# Sensor_Board.net
KiCad netlist of a schematic drawn in EAGLE
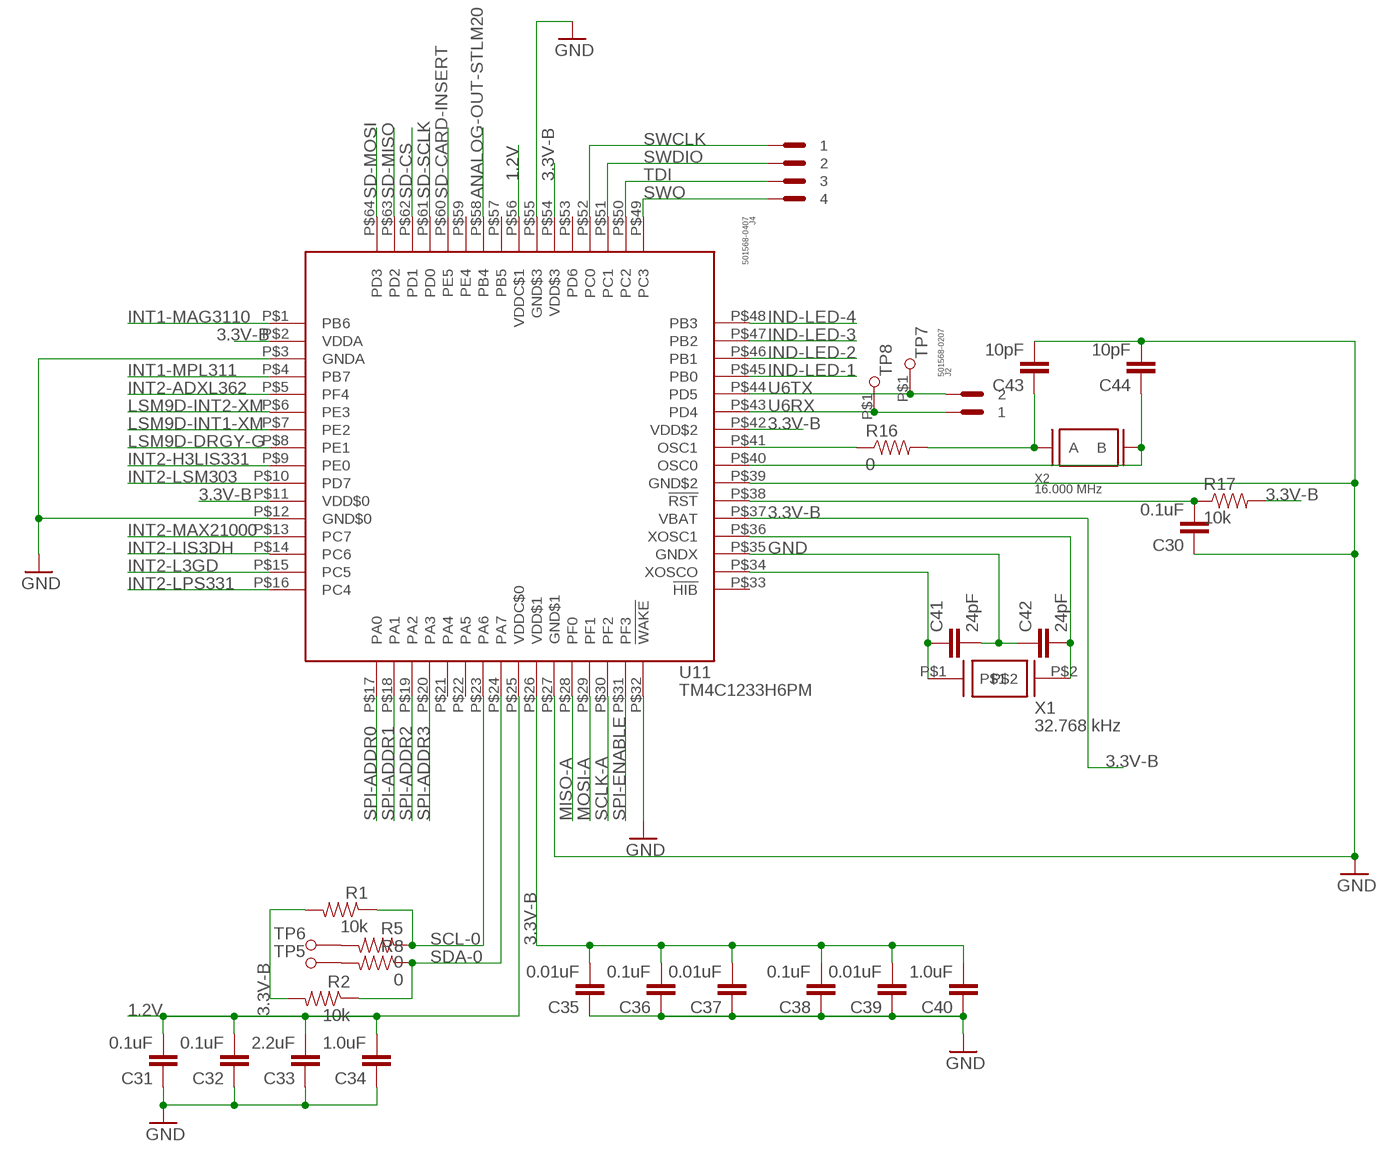
[diagram p0: schematic, sheet 1]
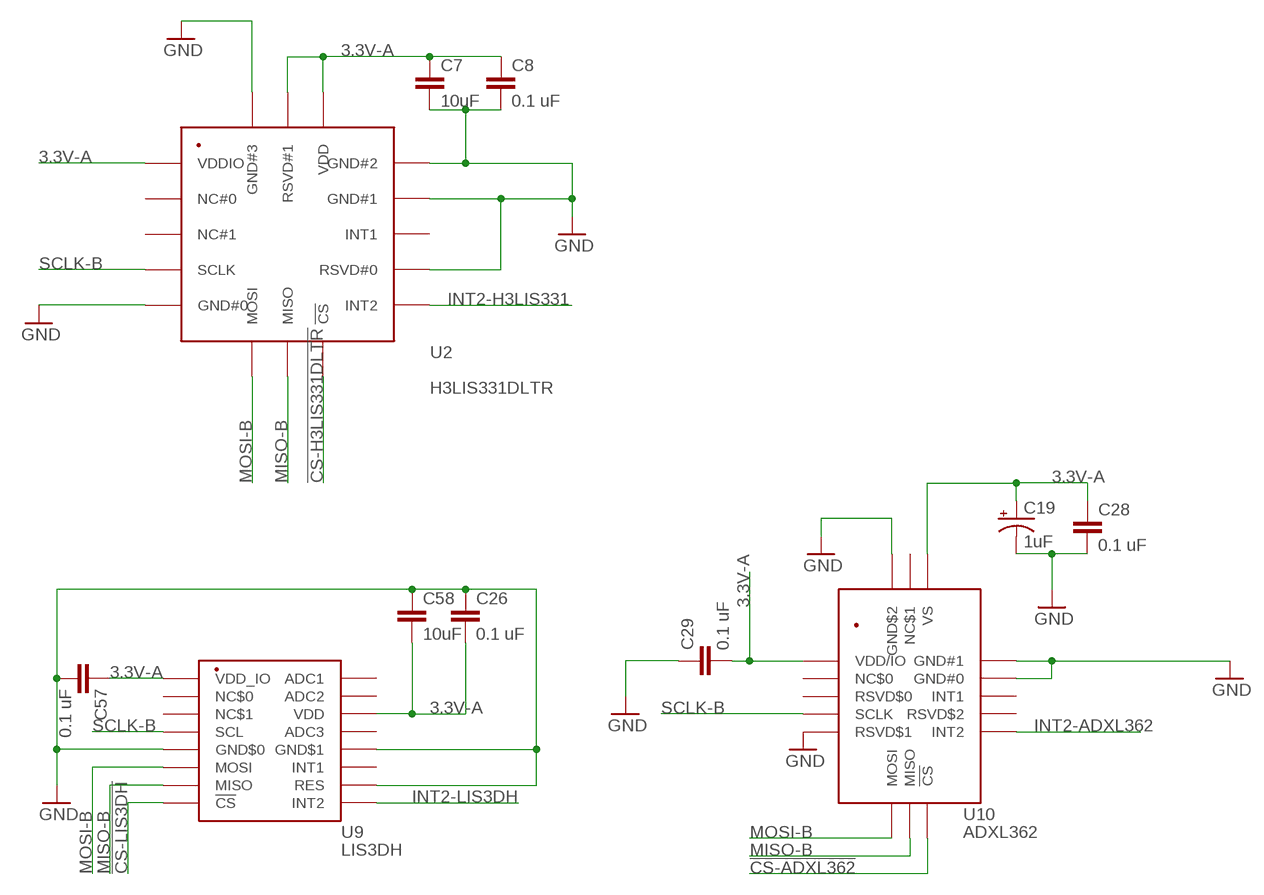
[diagram p1: schematic, sheet 2]
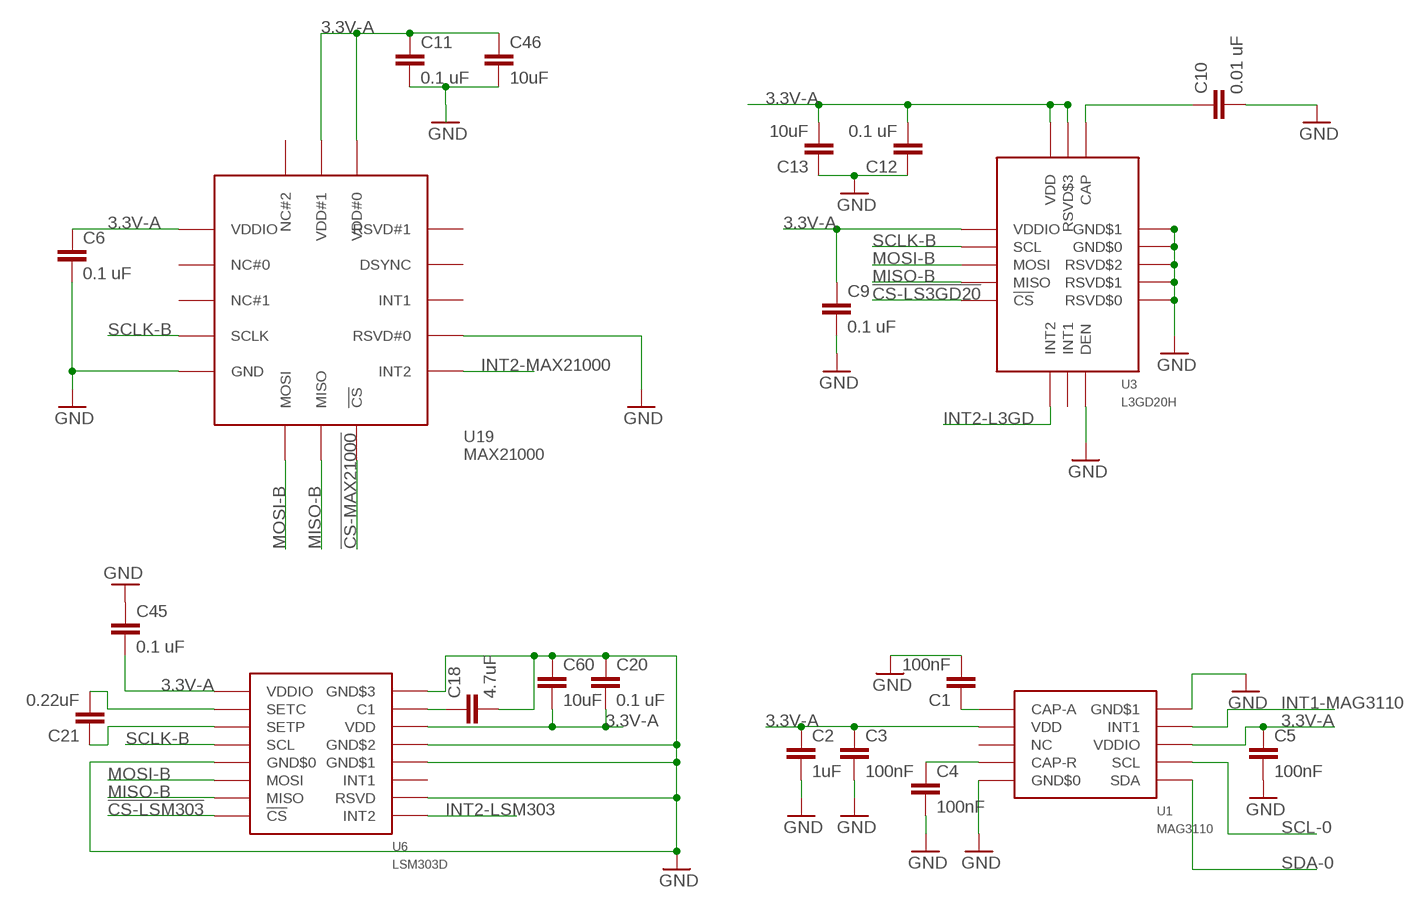
[diagram p2: schematic, sheet 3]
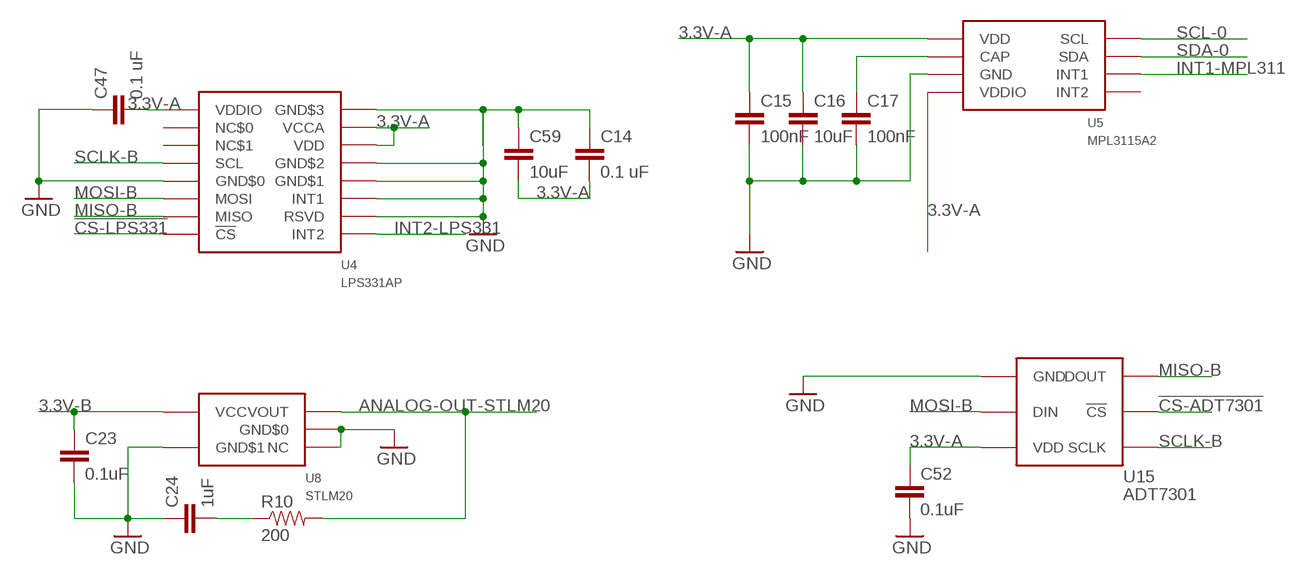
[diagram p3: schematic, sheet 4]
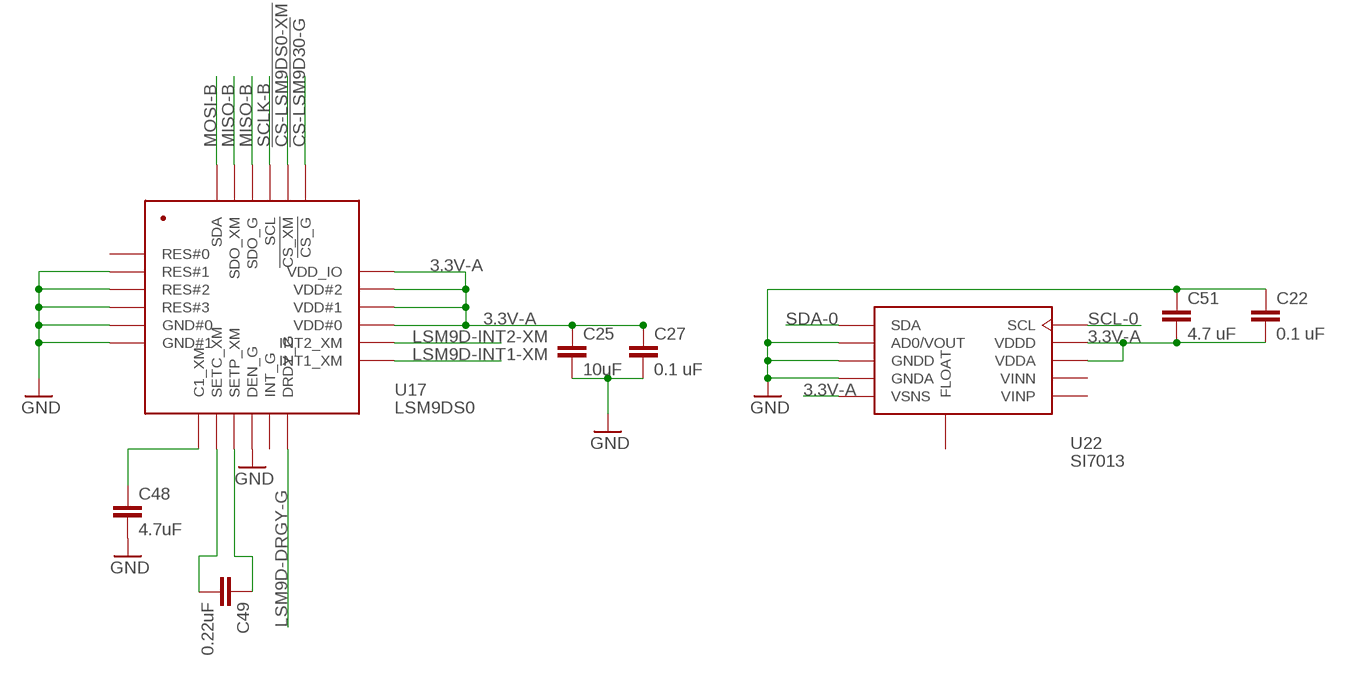
[diagram p4: schematic, sheet 5]
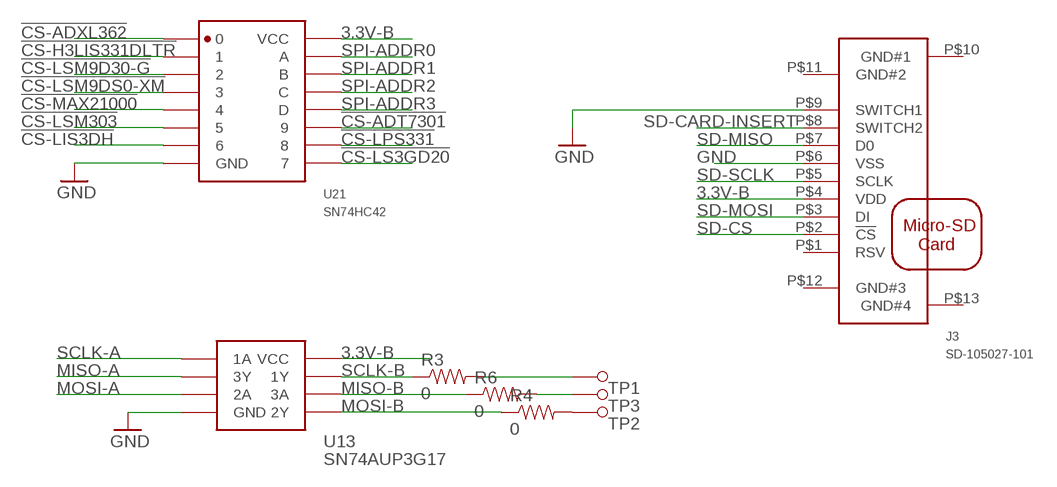
[diagram p5: schematic, sheet 6]
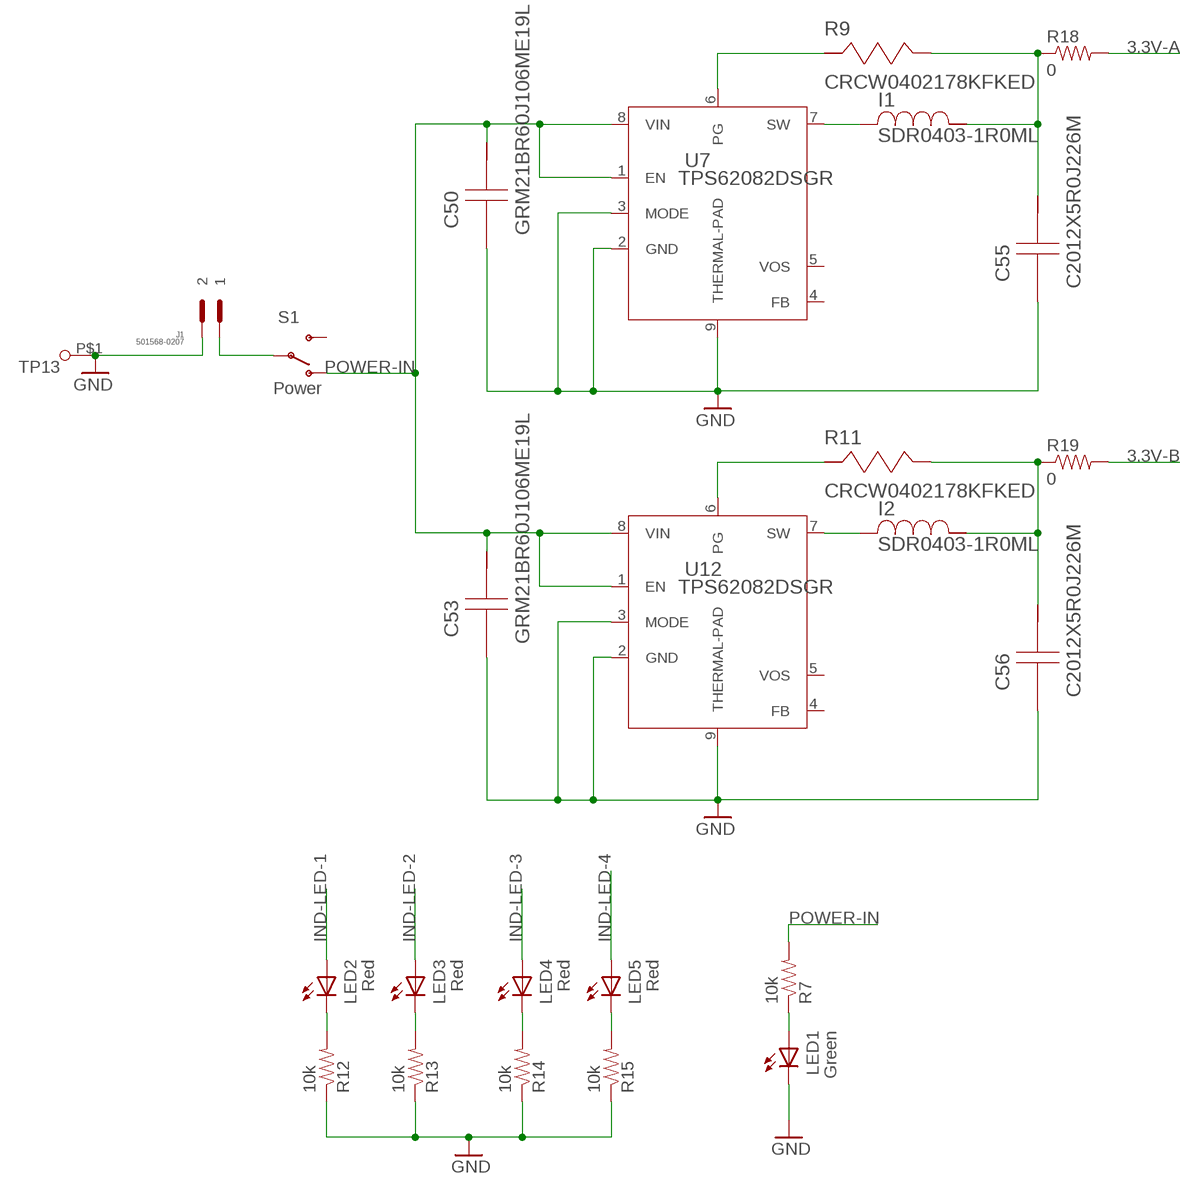
[diagram p6: schematic, sheet 7]

(export (version "E")
  (design (tool "Eeschema 10.0.6"))
  (components
    (comp (ref "J3")
      (value "SD-105027-101")
      (footprint "eagle-import:SD-105027-1001")
      (libsource (lib "eagle-import") (part "SD-105027-101"))
    )
    (comp (ref "R3")
      (value "0")
      (footprint "eagle-import:R0402")
      (libsource (lib "eagle-import") (part "RESISTOR"))
    )
    (comp (ref "R4")
      (value "0")
      (footprint "eagle-import:R0402")
      (libsource (lib "eagle-import") (part "RESISTOR"))
    )
    (comp (ref "R6")
      (value "0")
      (footprint "eagle-import:R0402")
      (libsource (lib "eagle-import") (part "RESISTOR"))
    )
    (comp (ref "TP1")
      (value "TESTPAD(ROUND)")
      (footprint "eagle-import:TESTPAD(ROUND)")
      (libsource (lib "eagle-import") (part "TESTPAD(ROUND)"))
    )
    (comp (ref "TP2")
      (value "TESTPAD(ROUND)")
      (footprint "eagle-import:TESTPAD(ROUND)")
      (libsource (lib "eagle-import") (part "TESTPAD(ROUND)"))
    )
    (comp (ref "TP3")
      (value "TESTPAD(ROUND)")
      (footprint "eagle-import:TESTPAD(ROUND)")
      (libsource (lib "eagle-import") (part "TESTPAD(ROUND)"))
    )
    (comp (ref "U13")
      (value "SN74AUP3G17")
      (footprint "eagle-import:8-VFSOP")
      (libsource (lib "eagle-import") (part "SN74AUP3G17"))
    )
    (comp (ref "U21")
      (value "SN74HC42")
      (footprint "eagle-import:SOIC-16")
      (libsource (lib "eagle-import") (part "SN74HC42"))
    )
    (comp (ref "C1")
      (value "100nF")
      (footprint "eagle-import:C0402")
      (libsource (lib "eagle-import") (part "CAPACITOR0402"))
    )
    (comp (ref "C2")
      (value "1uF")
      (footprint "eagle-import:C0402")
      (libsource (lib "eagle-import") (part "CAPACITOR0402"))
    )
    (comp (ref "C3")
      (value "100nF")
      (footprint "eagle-import:C0402")
      (libsource (lib "eagle-import") (part "CAPACITOR0402"))
    )
    (comp (ref "C4")
      (value "100nF")
      (footprint "eagle-import:C0402")
      (libsource (lib "eagle-import") (part "CAPACITOR0402"))
    )
    (comp (ref "C5")
      (value "100nF")
      (footprint "eagle-import:C0402")
      (libsource (lib "eagle-import") (part "CAPACITOR0402"))
    )
    (comp (ref "C6")
      (value "0.1 uF")
      (footprint "eagle-import:C0402")
      (fields
        (field (name "MANUFACTURER") "MURATA")
        (field (name "MANUFACTURER_PART_NUMBER") "GRM155R71A104KA01D")
        (field (name "NEWARK_PART_NUMBER") "14T3276")
      )
      (libsource (lib "eagle-import") (part "CAPACITOR0.1U-X7R-10%-10V"))
    )
    (comp (ref "C9")
      (value "0.1 uF")
      (footprint "eagle-import:C0402")
      (fields
        (field (name "MANUFACTURER") "TDK")
        (field (name "MANUFACTURER_PART_NUMBER") "CGA2B3X7R1E104K050BB")
        (field (name "NEWARK_PART_NUMBER") "04X3147")
      )
      (libsource (lib "eagle-import") (part "CAPACITOR0.1U-X7R-10%-25V"))
    )
    (comp (ref "C10")
      (value "0.01 uF")
      (footprint "eagle-import:C0402")
      (fields
        (field (name "MANUFACTURER") "MURATA")
        (field (name "MANUFACTURER_PART_NUMBER") "GRM155R71H103KA88D")
        (field (name "NEWARK_PART_NUMBER") "14T3284")
      )
      (libsource (lib "eagle-import") (part "CAPACITOR0.01U-X7R-10%-50V"))
    )
    (comp (ref "C11")
      (value "0.1 uF")
      (footprint "eagle-import:C0402")
      (fields
        (field (name "MANUFACTURER") "MURATA")
        (field (name "MANUFACTURER_PART_NUMBER") "GRM155R71A104KA01D")
        (field (name "NEWARK_PART_NUMBER") "14T3276")
      )
      (libsource (lib "eagle-import") (part "CAPACITOR0.1U-X7R-10%-10V"))
    )
    (comp (ref "C12")
      (value "0.1 uF")
      (footprint "eagle-import:C0402")
      (fields
        (field (name "MANUFACTURER") "TDK")
        (field (name "MANUFACTURER_PART_NUMBER") "CGA2B3X7R1E104K050BB")
        (field (name "NEWARK_PART_NUMBER") "04X3147")
      )
      (libsource (lib "eagle-import") (part "CAPACITOR0.1U-X7R-10%-25V"))
    )
    (comp (ref "C13")
      (value "10uF")
      (footprint "eagle-import:C0603")
      (fields
        (field (name "MANUFACTURER") "TDK")
        (field (name "MANUFACTURER_PART_NUMBER") "C1608X5R0J106K080AB")
        (field (name "NEWARK_PART_NUMBER") "04X3239")
      )
      (libsource (lib "eagle-import") (part "CAPACITOR10U-X5R-10%-6.3V"))
    )
    (comp (ref "C18")
      (value "4.7uF")
      (footprint "eagle-import:C0603")
      (fields
        (field (name "MANUFACTURER") "MURATA")
        (field (name "MANUFACTURER_PART_NUMBER") "GRM188R61E475KE11D")
        (field (name "NEWARK_PART_NUMBER") "68X2788")
      )
      (libsource (lib "eagle-import") (part "CAPACITOR4.7U-X5R-10%-25V"))
    )
    (comp (ref "C20")
      (value "0.1 uF")
      (footprint "eagle-import:C0402")
      (fields
        (field (name "MANUFACTURER") "TDK")
        (field (name "MANUFACTURER_PART_NUMBER") "CGA2B3X7R1E104K050BB")
        (field (name "NEWARK_PART_NUMBER") "04X3147")
      )
      (libsource (lib "eagle-import") (part "CAPACITOR0.1U-X7R-10%-25V"))
    )
    (comp (ref "C21")
      (value "0.22uF")
      (footprint "eagle-import:C0603")
      (fields
        (field (name "MANUFACTURER") "Taiyo Yuden")
        (field (name "MANUFACTURER_PART_NUMBER") "UMK107B7224KA-TR")
        (field (name "NEWARK_PART_NUMBER") "29X1406")
      )
      (libsource (lib "eagle-import") (part "CAPACITOR0.22U-X7R-10%-50V"))
    )
    (comp (ref "C45")
      (value "0.1 uF")
      (footprint "eagle-import:C0402")
      (fields
        (field (name "MANUFACTURER") "TDK")
        (field (name "MANUFACTURER_PART_NUMBER") "CGA2B3X7R1E104K050BB")
        (field (name "NEWARK_PART_NUMBER") "04X3147")
      )
      (libsource (lib "eagle-import") (part "CAPACITOR0.1U-X7R-10%-25V"))
    )
    (comp (ref "C46")
      (value "10uF")
      (footprint "eagle-import:C0603")
      (fields
        (field (name "MANUFACTURER") "TDK")
        (field (name "MANUFACTURER_PART_NUMBER") "C1068X5R1A106K080AC")
        (field (name "NEWARK_PART_NUMBER") "04X3243")
      )
      (libsource (lib "eagle-import") (part "CAPACITOR10U-X5R-10%-10V"))
    )
    (comp (ref "C60")
      (value "10uF")
      (footprint "eagle-import:C0603")
      (fields
        (field (name "MANUFACTURER") "TDK")
        (field (name "MANUFACTURER_PART_NUMBER") "C1608X5R0J106K080AB")
        (field (name "NEWARK_PART_NUMBER") "04X3239")
      )
      (libsource (lib "eagle-import") (part "CAPACITOR10U-X5R-10%-6.3V"))
    )
    (comp (ref "U1")
      (value "MAG3110")
      (footprint "eagle-import:DFN-10(2X2)")
      (libsource (lib "eagle-import") (part "MAG3110"))
    )
    (comp (ref "U3")
      (value "L3GD20H")
      (footprint "eagle-import:LGA-16(3X3)")
      (libsource (lib "eagle-import") (part "L3GD20H"))
    )
    (comp (ref "U6")
      (value "LSM303D")
      (footprint "eagle-import:LGA-16(3X3)")
      (libsource (lib "eagle-import") (part "LSM303D"))
    )
    (comp (ref "U19")
      (value "MAX21000")
      (footprint "eagle-import:LGA-16(3X3)")
      (libsource (lib "eagle-import") (part "MAX21000"))
    )
    (comp (ref "C50")
      (value "GRM21BR60J106ME19L")
      (footprint "eagle-import:0805")
      (libsource (lib "eagle-import") (part "GRM21BR60J106ME19L"))
    )
    (comp (ref "C53")
      (value "GRM21BR60J106ME19L")
      (footprint "eagle-import:0805")
      (libsource (lib "eagle-import") (part "GRM21BR60J106ME19L"))
    )
    (comp (ref "C55")
      (value "C2012X5R0J226M")
      (footprint "eagle-import:0805")
      (libsource (lib "eagle-import") (part "C2012X5R0J226M"))
    )
    (comp (ref "C56")
      (value "C2012X5R0J226M")
      (footprint "eagle-import:0805")
      (libsource (lib "eagle-import") (part "C2012X5R0J226M"))
    )
    (comp (ref "I1")
      (value "SDR0403-1R0ML")
      (footprint "eagle-import:SDR0403")
      (libsource (lib "eagle-import") (part "SDR0403-1R0ML"))
    )
    (comp (ref "I2")
      (value "SDR0403-1R0ML")
      (footprint "eagle-import:SDR0403")
      (libsource (lib "eagle-import") (part "SDR0403-1R0ML"))
    )
    (comp (ref "J1")
      (value "501568-0207")
      (footprint "eagle-import:501568-0207")
      (libsource (lib "eagle-import") (part "501568-0207"))
    )
    (comp (ref "LED1")
      (value "Green")
      (footprint "eagle-import:LED_0402")
      (fields (field (name "MANUFACTURER") "Knightbright") (field (name "PART_NUMBER") "APG1005CGC-T"))
      (libsource (lib "eagle-import") (part "LEDG"))
    )
    (comp (ref "LED2")
      (value "Red")
      (footprint "eagle-import:LED_0402")
      (fields (field (name "MANUFACTURER") "Knightbright") (field (name "PART_NUMBER") "APG1005SEC/E-T"))
      (libsource (lib "eagle-import") (part "LEDR"))
    )
    (comp (ref "LED3")
      (value "Red")
      (footprint "eagle-import:LED_0402")
      (fields (field (name "MANUFACTURER") "Knightbright") (field (name "PART_NUMBER") "APG1005SEC/E-T"))
      (libsource (lib "eagle-import") (part "LEDR"))
    )
    (comp (ref "LED4")
      (value "Red")
      (footprint "eagle-import:LED_0402")
      (fields (field (name "MANUFACTURER") "Knightbright") (field (name "PART_NUMBER") "APG1005SEC/E-T"))
      (libsource (lib "eagle-import") (part "LEDR"))
    )
    (comp (ref "LED5")
      (value "Red")
      (footprint "eagle-import:LED_0402")
      (fields (field (name "MANUFACTURER") "Knightbright") (field (name "PART_NUMBER") "APG1005SEC/E-T"))
      (libsource (lib "eagle-import") (part "LEDR"))
    )
    (comp (ref "R7")
      (value "10k")
      (footprint "eagle-import:R0402")
      (libsource (lib "eagle-import") (part "RESISTOR"))
    )
    (comp (ref "R9")
      (value "CRCW0402178KFKED")
      (footprint "eagle-import:0402")
      (fields (field (name "POWER") "0.063") (field (name "TOLERANCE") "1.0"))
      (libsource (lib "eagle-import") (part "CRCW0402178KFKED"))
    )
    (comp (ref "R11")
      (value "CRCW0402178KFKED")
      (footprint "eagle-import:0402")
      (fields (field (name "POWER") "0.063") (field (name "TOLERANCE") "1.0"))
      (libsource (lib "eagle-import") (part "CRCW0402178KFKED"))
    )
    (comp (ref "R12")
      (value "10k")
      (footprint "eagle-import:R0402")
      (libsource (lib "eagle-import") (part "RESISTOR"))
    )
    (comp (ref "R13")
      (value "10k")
      (footprint "eagle-import:R0402")
      (libsource (lib "eagle-import") (part "RESISTOR"))
    )
    (comp (ref "R14")
      (value "10k")
      (footprint "eagle-import:R0402")
      (libsource (lib "eagle-import") (part "RESISTOR"))
    )
    (comp (ref "R15")
      (value "10k")
      (footprint "eagle-import:R0402")
      (libsource (lib "eagle-import") (part "RESISTOR"))
    )
    (comp (ref "R18")
      (value "0")
      (footprint "eagle-import:0603-RES")
      (libsource (lib "eagle-import") (part "RESISTOR0603-RES"))
    )
    (comp (ref "R19")
      (value "0")
      (footprint "eagle-import:0603-RES")
      (libsource (lib "eagle-import") (part "RESISTOR0603-RES"))
    )
    (comp (ref "S1")
      (value "Power")
      (footprint "eagle-import:SWITCH-SPST-SMD-A")
      (libsource (lib "eagle-import") (part "SWITCH-SPDT-SMD-A"))
    )
    (comp (ref "TP13")
      (value "TESTPAD(ROUND)")
      (footprint "eagle-import:TESTPAD(ROUND)")
      (libsource (lib "eagle-import") (part "Kas-Passives_TESTPAD(ROUND)"))
    )
    (comp (ref "U7")
      (value "TPS62082DSGR")
      (footprint "eagle-import:S-PWSON-N8")
      (libsource (lib "eagle-import") (part "TPS62082DSGR"))
    )
    (comp (ref "U12")
      (value "TPS62082DSGR")
      (footprint "eagle-import:S-PWSON-N8")
      (libsource (lib "eagle-import") (part "TPS62082DSGR"))
    )
    (comp (ref "C22")
      (value "0.1 uF")
      (footprint "eagle-import:C0402")
      (fields
        (field (name "MANUFACTURER") "MURATA")
        (field (name "MANUFACTURER_PART_NUMBER") "GRM155R71A104KA01D")
        (field (name "NEWARK_PART_NUMBER") "14T3276")
      )
      (libsource (lib "eagle-import") (part "CAPACITOR0.1U-X7R-10%-10V"))
    )
    (comp (ref "C25")
      (value "10uF")
      (footprint "eagle-import:C0603")
      (fields
        (field (name "MANUFACTURER") "TDK")
        (field (name "MANUFACTURER_PART_NUMBER") "C1068X5R1A106K080AC")
        (field (name "NEWARK_PART_NUMBER") "04X3243")
      )
      (libsource (lib "eagle-import") (part "CAPACITOR10U-X5R-10%-10V"))
    )
    (comp (ref "C27")
      (value "0.1 uF")
      (footprint "eagle-import:C0402")
      (fields
        (field (name "MANUFACTURER") "AVX")
        (field (name "MANUFACTURER_PART_NUMBER") "0402YC104KAT2A")
        (field (name "NEWARK_PART_NUMBER") "09R7024")
      )
      (libsource (lib "eagle-import") (part "CAPACITOR0.1U-X7R-10%-16V"))
    )
    (comp (ref "C48")
      (value "4.7uF")
      (footprint "eagle-import:C0603")
      (fields
        (field (name "MANUFACTURER") "MURATA")
        (field (name "MANUFACTURER_PART_NUMBER") "GRM21BF51A475ZA01L")
        (field (name "NEWARK_PART_NUMBER") "14T3337")
      )
      (libsource (lib "eagle-import") (part "CAPACITOR4.7U-Y5V--20+80-10V"))
    )
    (comp (ref "C49")
      (value "0.22uF")
      (footprint "eagle-import:C0402")
      (libsource (lib "eagle-import") (part "CAPACITOR0402"))
    )
    (comp (ref "C51")
      (value "4.7 uF")
      (footprint "eagle-import:C0402")
      (fields
        (field (name "MANUFACTURER") "TDK")
        (field (name "MANUFACTURER_PART_NUMBER") "C1005X5R0J475K050BC")
        (field (name "NEWARK_PART_NUMBER") "04X3211")
      )
      (libsource (lib "eagle-import") (part "CAPACITOR4.7U-X5R-10%-6.3V"))
    )
    (comp (ref "U17")
      (value "LSM9DS0")
      (footprint "eagle-import:LGA-24(4X4)")
      (libsource (lib "eagle-import") (part "LSM9DS0"))
    )
    (comp (ref "U22")
      (value "SI7013")
      (footprint "eagle-import:DFN-10(3X3)")
      (libsource (lib "eagle-import") (part "SI7013"))
    )
    (comp (ref "C7")
      (value "10uF")
      (footprint "eagle-import:C0603")
      (fields
        (field (name "MANUFACTURER") "TDK")
        (field (name "MANUFACTURER_PART_NUMBER") "C1608X5R0J106K080AB")
        (field (name "NEWARK_PART_NUMBER") "04X3239")
      )
      (libsource (lib "eagle-import") (part "CAPACITOR10U-X5R-10%-6.3V"))
    )
    (comp (ref "C8")
      (value "0.1 uF")
      (footprint "eagle-import:C0402")
      (fields
        (field (name "MANUFACTURER") "TDK")
        (field (name "MANUFACTURER_PART_NUMBER") "CGA2B3X7R1E104K050BB")
        (field (name "NEWARK_PART_NUMBER") "04X3147")
      )
      (libsource (lib "eagle-import") (part "CAPACITOR0.1U-X7R-10%-25V"))
    )
    (comp (ref "C19")
      (value "1uF")
      (footprint "eagle-import:EIA6032")
      (libsource (lib "eagle-import") (part "CAP_POL6032"))
    )
    (comp (ref "C26")
      (value "0.1 uF")
      (footprint "eagle-import:C0402")
      (fields
        (field (name "MANUFACTURER") "TDK")
        (field (name "MANUFACTURER_PART_NUMBER") "CGA2B3X7R1E104K050BB")
        (field (name "NEWARK_PART_NUMBER") "04X3147")
      )
      (libsource (lib "eagle-import") (part "CAPACITOR0.1U-X7R-10%-25V"))
    )
    (comp (ref "C28")
      (value "0.1 uF")
      (footprint "eagle-import:C0402")
      (fields
        (field (name "MANUFACTURER") "TDK")
        (field (name "MANUFACTURER_PART_NUMBER") "C1005X7R1H104K050BB")
        (field (name "NEWARK_PART_NUMBER") "04X3230")
      )
      (libsource (lib "eagle-import") (part "CAPACITOR0.1U-X7R-10%-50V"))
    )
    (comp (ref "C29")
      (value "0.1 uF")
      (footprint "eagle-import:C0402")
      (fields
        (field (name "MANUFACTURER") "TDK")
        (field (name "MANUFACTURER_PART_NUMBER") "C1005X7R1H104K050BB")
        (field (name "NEWARK_PART_NUMBER") "04X3230")
      )
      (libsource (lib "eagle-import") (part "CAPACITOR0.1U-X7R-10%-50V"))
    )
    (comp (ref "C57")
      (value "0.1 uF")
      (footprint "eagle-import:C0402")
      (fields
        (field (name "MANUFACTURER") "TDK")
        (field (name "MANUFACTURER_PART_NUMBER") "CGA2B3X7R1E104K050BB")
        (field (name "NEWARK_PART_NUMBER") "04X3147")
      )
      (libsource (lib "eagle-import") (part "CAPACITOR0.1U-X7R-10%-25V"))
    )
    (comp (ref "C58")
      (value "10uF")
      (footprint "eagle-import:C0603")
      (fields
        (field (name "MANUFACTURER") "TDK")
        (field (name "MANUFACTURER_PART_NUMBER") "C1608X5R0J106K080AB")
        (field (name "NEWARK_PART_NUMBER") "04X3239")
      )
      (libsource (lib "eagle-import") (part "CAPACITOR10U-X5R-10%-6.3V"))
    )
    (comp (ref "U2")
      (value "H3LIS331DLTR")
      (footprint "eagle-import:LGA-16(3X3)")
      (libsource (lib "eagle-import") (part "H3LIS331DLTR"))
    )
    (comp (ref "U9")
      (value "LIS3DH")
      (footprint "eagle-import:LGA-16(3X3)")
      (libsource (lib "eagle-import") (part "LIS3DH"))
    )
    (comp (ref "U10")
      (value "ADXL362")
      (footprint "eagle-import:LGA-16(3X3.25)")
      (libsource (lib "eagle-import") (part "ADXL362"))
    )
    (comp (ref "C30")
      (value "0.1uF")
      (footprint "eagle-import:C0402")
      (libsource (lib "eagle-import") (part "CAPACITOR0402"))
    )
    (comp (ref "C31")
      (value "0.1uF")
      (footprint "eagle-import:C0402")
      (libsource (lib "eagle-import") (part "CAPACITOR0402"))
    )
    (comp (ref "C32")
      (value "0.1uF")
      (footprint "eagle-import:C0402")
      (libsource (lib "eagle-import") (part "CAPACITOR0402"))
    )
    (comp (ref "C33")
      (value "2.2uF")
      (footprint "eagle-import:C0402")
      (libsource (lib "eagle-import") (part "CAPACITOR0402"))
    )
    (comp (ref "C34")
      (value "1.0uF")
      (footprint "eagle-import:C0402")
      (libsource (lib "eagle-import") (part "CAPACITOR0402"))
    )
    (comp (ref "C35")
      (value "0.01uF")
      (footprint "eagle-import:C0402")
      (libsource (lib "eagle-import") (part "CAPACITOR0402"))
    )
    (comp (ref "C36")
      (value "0.1uF")
      (footprint "eagle-import:C0402")
      (libsource (lib "eagle-import") (part "CAPACITOR0402"))
    )
    (comp (ref "C37")
      (value "0.01uF")
      (footprint "eagle-import:C0402")
      (libsource (lib "eagle-import") (part "CAPACITOR0402"))
    )
    (comp (ref "C38")
      (value "0.1uF")
      (footprint "eagle-import:C0402")
      (libsource (lib "eagle-import") (part "CAPACITOR0402"))
    )
    (comp (ref "C39")
      (value "0.01uF")
      (footprint "eagle-import:C0402")
      (libsource (lib "eagle-import") (part "CAPACITOR0402"))
    )
    (comp (ref "C40")
      (value "1.0uF")
      (footprint "eagle-import:C0402")
      (libsource (lib "eagle-import") (part "CAPACITOR0402"))
    )
    (comp (ref "C41")
      (value "24pF")
      (footprint "eagle-import:C0402")
      (libsource (lib "eagle-import") (part "CAPACITOR0402"))
    )
    (comp (ref "C42")
      (value "24pF")
      (footprint "eagle-import:C0402")
      (libsource (lib "eagle-import") (part "CAPACITOR0402"))
    )
    (comp (ref "C43")
      (value "10pF")
      (footprint "eagle-import:C0402")
      (libsource (lib "eagle-import") (part "CAPACITOR0402"))
    )
    (comp (ref "C44")
      (value "10pF")
      (footprint "eagle-import:C0402")
      (libsource (lib "eagle-import") (part "CAPACITOR0402"))
    )
    (comp (ref "J2")
      (value "501568-0207")
      (footprint "eagle-import:501568-0207")
      (libsource (lib "eagle-import") (part "501568-0207"))
    )
    (comp (ref "J4")
      (value "501568-0407")
      (footprint "eagle-import:501568-0407")
      (libsource (lib "eagle-import") (part "501568-0407"))
    )
    (comp (ref "R1")
      (value "10k")
      (footprint "eagle-import:R0402")
      (libsource (lib "eagle-import") (part "RESISTOR"))
    )
    (comp (ref "R2")
      (value "10k")
      (footprint "eagle-import:R0402")
      (libsource (lib "eagle-import") (part "RESISTOR"))
    )
    (comp (ref "R5")
      (value "0")
      (footprint "eagle-import:R0402")
      (libsource (lib "eagle-import") (part "RESISTOR"))
    )
    (comp (ref "R8")
      (value "0")
      (footprint "eagle-import:R0402")
      (libsource (lib "eagle-import") (part "RESISTOR"))
    )
    (comp (ref "R16")
      (value "0")
      (footprint "eagle-import:R0402")
      (libsource (lib "eagle-import") (part "RESISTOR"))
    )
    (comp (ref "R17")
      (value "10k")
      (footprint "eagle-import:R0402")
      (libsource (lib "eagle-import") (part "RESISTOR"))
    )
    (comp (ref "TP5")
      (value "TESTPAD(ROUND)")
      (footprint "eagle-import:TESTPAD(ROUND)")
      (libsource (lib "eagle-import") (part "TESTPAD(ROUND)"))
    )
    (comp (ref "TP6")
      (value "TESTPAD(ROUND)")
      (footprint "eagle-import:TESTPAD(ROUND)")
      (libsource (lib "eagle-import") (part "TESTPAD(ROUND)"))
    )
    (comp (ref "TP7")
      (value "TESTPAD(ROUND)")
      (footprint "eagle-import:TESTPAD(ROUND)")
      (libsource (lib "eagle-import") (part "Kas-Passives_TESTPAD(ROUND)"))
    )
    (comp (ref "TP8")
      (value "TESTPAD(ROUND)")
      (footprint "eagle-import:TESTPAD(ROUND)")
      (libsource (lib "eagle-import") (part "Kas-Passives_TESTPAD(ROUND)"))
    )
    (comp (ref "U11")
      (value "TM4C1233H6PM")
      (footprint "eagle-import:S-PQFP-G64")
      (libsource (lib "eagle-import") (part "TM4C1233H6PM"))
    )
    (comp (ref "X1")
      (value "32.768 kHz")
      (footprint "eagle-import:2-SMD(3.2X1.5)")
      (libsource (lib "eagle-import") (part "ABS07L"))
    )
    (comp (ref "X2")
      (value "16.000 MHz")
      (footprint "eagle-import:4-SMD(3.2X2.5)")
      (libsource (lib "eagle-import") (part "NX3225GA"))
    )
    (comp (ref "C14")
      (value "0.1 uF")
      (footprint "eagle-import:C0402")
      (fields
        (field (name "MANUFACTURER") "TDK")
        (field (name "MANUFACTURER_PART_NUMBER") "CGA2B3X7R1E104K050BB")
        (field (name "NEWARK_PART_NUMBER") "04X3147")
      )
      (libsource (lib "eagle-import") (part "CAPACITOR0.1U-X7R-10%-25V"))
    )
    (comp (ref "C15")
      (value "100nF")
      (footprint "eagle-import:C0402")
      (libsource (lib "eagle-import") (part "CAPACITOR0402"))
    )
    (comp (ref "C16")
      (value "10uF")
      (footprint "eagle-import:C0402")
      (libsource (lib "eagle-import") (part "CAPACITOR0402"))
    )
    (comp (ref "C17")
      (value "100nF")
      (footprint "eagle-import:C0402")
      (libsource (lib "eagle-import") (part "CAPACITOR0402"))
    )
    (comp (ref "C23")
      (value "0.1uF")
      (footprint "eagle-import:C0402")
      (libsource (lib "eagle-import") (part "CAPACITOR0402"))
    )
    (comp (ref "C24")
      (value "1uF")
      (footprint "eagle-import:C0402")
      (libsource (lib "eagle-import") (part "CAPACITOR0402"))
    )
    (comp (ref "C47")
      (value "0.1 uF")
      (footprint "eagle-import:C0402")
      (fields
        (field (name "MANUFACTURER") "TDK")
        (field (name "MANUFACTURER_PART_NUMBER") "CGA2B3X7R1E104K050BB")
        (field (name "NEWARK_PART_NUMBER") "04X3147")
      )
      (libsource (lib "eagle-import") (part "CAPACITOR0.1U-X7R-10%-25V"))
    )
    (comp (ref "C52")
      (value "0.1uF")
      (footprint "eagle-import:C0402")
      (libsource (lib "eagle-import") (part "CAPACITOR0402"))
    )
    (comp (ref "C59")
      (value "10uF")
      (footprint "eagle-import:C0603")
      (fields
        (field (name "MANUFACTURER") "TDK")
        (field (name "MANUFACTURER_PART_NUMBER") "C1608X5R0J106K080AB")
        (field (name "NEWARK_PART_NUMBER") "04X3239")
      )
      (libsource (lib "eagle-import") (part "CAPACITOR10U-X5R-10%-6.3V"))
    )
    (comp (ref "R10")
      (value "200")
      (footprint "eagle-import:R0402")
      (libsource (lib "eagle-import") (part "RESISTOR"))
    )
    (comp (ref "U4")
      (value "LPS331AP")
      (footprint "eagle-import:LGA-16(3X3)")
      (libsource (lib "eagle-import") (part "LPS331AP"))
    )
    (comp (ref "U5")
      (value "MPL3115A2")
      (footprint "eagle-import:LGA-8(5X3)")
      (libsource (lib "eagle-import") (part "MPL3115A2"))
    )
    (comp (ref "U8")
      (value "STLM20")
      (footprint "eagle-import:SOT323-5L")
      (libsource (lib "eagle-import") (part "STLM20"))
    )
    (comp (ref "U15")
      (value "ADT7301")
      (footprint "eagle-import:SOT23-6")
      (libsource (lib "eagle-import") (part "ADT7301"))
    )
  )
  (nets
    (net (code "1") (name "1.2V") (class "Default")
      (node (ref "C31") (pin "2") (pinfunction "2_2") (pintype "passive"))
      (node (ref "C32") (pin "2") (pinfunction "2_2") (pintype "passive"))
      (node (ref "C33") (pin "2") (pinfunction "2_2") (pintype "passive"))
      (node (ref "C34") (pin "2") (pinfunction "2_2") (pintype "passive"))
      (node (ref "U11") (pin "P$25") (pinfunction "VDDC$0_P$25") (pintype "bidirectional"))
      (node (ref "U11") (pin "P$56") (pinfunction "VDDC$1_P$56") (pintype "bidirectional"))
    )
    (net (code "2") (name "3.3V-A") (class "Default")
      (node (ref "C11") (pin "1") (pinfunction "1_1") (pintype "passive"))
      (node (ref "C12") (pin "2") (pinfunction "2_2") (pintype "passive"))
      (node (ref "C13") (pin "2") (pinfunction "2_2") (pintype "passive"))
      (node (ref "C14") (pin "2") (pinfunction "2_2") (pintype "passive"))
      (node (ref "C15") (pin "1") (pinfunction "1_1") (pintype "passive"))
      (node (ref "C16") (pin "1") (pinfunction "1_1") (pintype "passive"))
      (node (ref "C19") (pin "P$1") (pinfunction "+_P$1") (pintype "passive"))
      (node (ref "C2") (pin "1") (pinfunction "1_1") (pintype "passive"))
      (node (ref "C20") (pin "2") (pinfunction "2_2") (pintype "passive"))
      (node (ref "C22") (pin "2") (pinfunction "2_2") (pintype "passive"))
      (node (ref "C25") (pin "1") (pinfunction "1_1") (pintype "passive"))
      (node (ref "C26") (pin "2") (pinfunction "2_2") (pintype "passive"))
      (node (ref "C27") (pin "1") (pinfunction "1_1") (pintype "passive"))
      (node (ref "C28") (pin "1") (pinfunction "1_1") (pintype "passive"))
      (node (ref "C29") (pin "2") (pinfunction "2_2") (pintype "passive"))
      (node (ref "C3") (pin "1") (pinfunction "1_1") (pintype "passive"))
      (node (ref "C45") (pin "2") (pinfunction "2_2") (pintype "passive"))
      (node (ref "C46") (pin "1") (pinfunction "1_1") (pintype "passive"))
      (node (ref "C47") (pin "2") (pinfunction "2_2") (pintype "passive"))
      (node (ref "C5") (pin "1") (pinfunction "1_1") (pintype "passive"))
      (node (ref "C51") (pin "2") (pinfunction "2_2") (pintype "passive"))
      (node (ref "C52") (pin "1") (pinfunction "1_1") (pintype "passive"))
      (node (ref "C57") (pin "1") (pinfunction "1_1") (pintype "passive"))
      (node (ref "C58") (pin "2") (pinfunction "2_2") (pintype "passive"))
      (node (ref "C59") (pin "2") (pinfunction "2_2") (pintype "passive"))
      (node (ref "C6") (pin "1") (pinfunction "1_1") (pintype "passive"))
      (node (ref "C60") (pin "2") (pinfunction "2_2") (pintype "passive"))
      (node (ref "C7") (pin "1") (pinfunction "1_1") (pintype "passive"))
      (node (ref "C8") (pin "1") (pinfunction "1_1") (pintype "passive"))
      (node (ref "C9") (pin "1") (pinfunction "1_1") (pintype "passive"))
      (node (ref "R18") (pin "2") (pinfunction "2_2") (pintype "passive"))
      (node (ref "U1") (pin "P$2") (pinfunction "VDD_P$2") (pintype "bidirectional"))
      (node (ref "U1") (pin "P$8") (pinfunction "VDDIO_P$8") (pintype "bidirectional"))
      (node (ref "U10") (pin "P$1") (pinfunction "VDD/IO_P$1") (pintype "bidirectional"))
      (node (ref "U10") (pin "P$14") (pinfunction "VS_P$14") (pintype "bidirectional"))
      (node (ref "U15") (pin "P$3") (pinfunction "VDD_P$3") (pintype "bidirectional"))
      (node (ref "U17") (pin "P$15") (pinfunction "VDD#0_P$15") (pintype "bidirectional"))
      (node (ref "U17") (pin "P$16") (pinfunction "VDD#1_P$16") (pintype "bidirectional"))
      (node (ref "U17") (pin "P$17") (pinfunction "VDD#2_P$17") (pintype "bidirectional"))
      (node (ref "U17") (pin "P$18") (pinfunction "VDD_IO_P$18") (pintype "bidirectional"))
      (node (ref "U19") (pin "P$1") (pinfunction "VDDIO_P$1") (pintype "bidirectional"))
      (node (ref "U19") (pin "P$14") (pinfunction "VDD#0_P$14") (pintype "bidirectional"))
      (node (ref "U19") (pin "P$15") (pinfunction "VDD#1_P$15") (pintype "bidirectional"))
      (node (ref "U2") (pin "P$1") (pinfunction "VDDIO_P$1") (pintype "bidirectional"))
      (node (ref "U2") (pin "P$14") (pinfunction "VDD_P$14") (pintype "bidirectional"))
      (node (ref "U2") (pin "P$15") (pinfunction "RSVD#1_P$15") (pintype "bidirectional"))
      (node (ref "U22") (pin "P$5") (pinfunction "VSNS_P$5") (pintype "bidirectional"))
      (node (ref "U22") (pin "P$8") (pinfunction "VDDA_P$8") (pintype "bidirectional"))
      (node (ref "U22") (pin "P$9") (pinfunction "VDDD_P$9") (pintype "bidirectional"))
      (node (ref "U3") (pin "P$1") (pinfunction "VDDIO_P$1") (pintype "bidirectional"))
      (node (ref "U3") (pin "P$15") (pinfunction "RSVD$3_P$15") (pintype "bidirectional"))
      (node (ref "U3") (pin "P$16") (pinfunction "VDD_P$16") (pintype "bidirectional"))
      (node (ref "U4") (pin "P$1") (pinfunction "VDDIO_P$1") (pintype "bidirectional"))
      (node (ref "U4") (pin "P$14") (pinfunction "VDD_P$14") (pintype "bidirectional"))
      (node (ref "U4") (pin "P$15") (pinfunction "VCCA_P$15") (pintype "bidirectional"))
      (node (ref "U5") (pin "P$1") (pinfunction "VDD_P$1") (pintype "bidirectional"))
      (node (ref "U5") (pin "P$4") (pinfunction "VDDIO_P$4") (pintype "bidirectional"))
      (node (ref "U6") (pin "P$1") (pinfunction "VDDIO_P$1") (pintype "bidirectional"))
      (node (ref "U6") (pin "P$14") (pinfunction "VDD_P$14") (pintype "bidirectional"))
      (node (ref "U9") (pin "P$1") (pinfunction "VDD_IO_P$1") (pintype "bidirectional"))
      (node (ref "U9") (pin "P$14") (pinfunction "VDD_P$14") (pintype "bidirectional"))
    )
    (net (code "3") (name "3.3V-B") (class "Default")
      (node (ref "C23") (pin "1") (pinfunction "1_1") (pintype "passive"))
      (node (ref "C35") (pin "2") (pinfunction "2_2") (pintype "passive"))
      (node (ref "C36") (pin "2") (pinfunction "2_2") (pintype "passive"))
      (node (ref "C37") (pin "2") (pinfunction "2_2") (pintype "passive"))
      (node (ref "C38") (pin "2") (pinfunction "2_2") (pintype "passive"))
      (node (ref "C39") (pin "2") (pinfunction "2_2") (pintype "passive"))
      (node (ref "C40") (pin "2") (pinfunction "2_2") (pintype "passive"))
      (node (ref "J3") (pin "P$4") (pinfunction "VDD_P$4") (pintype "bidirectional"))
      (node (ref "R1") (pin "2") (pinfunction "2_2") (pintype "passive"))
      (node (ref "R17") (pin "2") (pinfunction "2_2") (pintype "passive"))
      (node (ref "R19") (pin "2") (pinfunction "2_2") (pintype "passive"))
      (node (ref "R2") (pin "2") (pinfunction "2_2") (pintype "passive"))
      (node (ref "U11") (pin "P$11") (pinfunction "VDD$0_P$11") (pintype "bidirectional"))
      (node (ref "U11") (pin "P$2") (pinfunction "VDDA_P$2") (pintype "bidirectional"))
      (node (ref "U11") (pin "P$26") (pinfunction "VDD$1_P$26") (pintype "bidirectional"))
      (node (ref "U11") (pin "P$37") (pinfunction "VBAT_P$37") (pintype "bidirectional"))
      (node (ref "U11") (pin "P$42") (pinfunction "VDD$2_P$42") (pintype "bidirectional"))
      (node (ref "U11") (pin "P$54") (pinfunction "VDD$3_P$54") (pintype "bidirectional"))
      (node (ref "U13") (pin "P$8") (pinfunction "VCC_P$8") (pintype "bidirectional"))
      (node (ref "U21") (pin "P$16") (pinfunction "VCC_P$16") (pintype "bidirectional"))
      (node (ref "U8") (pin "P$4") (pinfunction "VCC_P$4") (pintype "bidirectional"))
    )
    (net (code "4") (name "ANALOG-OUT-STLM20") (class "Default")
      (node (ref "R10") (pin "2") (pinfunction "2_2") (pintype "passive"))
      (node (ref "U11") (pin "P$58") (pinfunction "PB4_P$58") (pintype "bidirectional"))
      (node (ref "U8") (pin "P$3") (pinfunction "VOUT_P$3") (pintype "bidirectional"))
    )
    (net (code "5") (name "GND") (class "Default")
      (node (ref "C1") (pin "2") (pinfunction "2_2") (pintype "passive"))
      (node (ref "C10") (pin "2") (pinfunction "2_2") (pintype "passive"))
      (node (ref "C11") (pin "2") (pinfunction "2_2") (pintype "passive"))
      (node (ref "C12") (pin "1") (pinfunction "1_1") (pintype "passive"))
      (node (ref "C13") (pin "1") (pinfunction "1_1") (pintype "passive"))
      (node (ref "C14") (pin "1") (pinfunction "1_1") (pintype "passive"))
      (node (ref "C15") (pin "2") (pinfunction "2_2") (pintype "passive"))
      (node (ref "C16") (pin "2") (pinfunction "2_2") (pintype "passive"))
      (node (ref "C17") (pin "2") (pinfunction "2_2") (pintype "passive"))
      (node (ref "C18") (pin "2") (pinfunction "2_2") (pintype "passive"))
      (node (ref "C19") (pin "P$2") (pinfunction "-_P$2") (pintype "passive"))
      (node (ref "C2") (pin "2") (pinfunction "2_2") (pintype "passive"))
      (node (ref "C20") (pin "1") (pinfunction "1_1") (pintype "passive"))
      (node (ref "C22") (pin "1") (pinfunction "1_1") (pintype "passive"))
      (node (ref "C23") (pin "2") (pinfunction "2_2") (pintype "passive"))
      (node (ref "C24") (pin "1") (pinfunction "1_1") (pintype "passive"))
      (node (ref "C25") (pin "2") (pinfunction "2_2") (pintype "passive"))
      (node (ref "C26") (pin "1") (pinfunction "1_1") (pintype "passive"))
      (node (ref "C27") (pin "2") (pinfunction "2_2") (pintype "passive"))
      (node (ref "C28") (pin "2") (pinfunction "2_2") (pintype "passive"))
      (node (ref "C29") (pin "1") (pinfunction "1_1") (pintype "passive"))
      (node (ref "C3") (pin "2") (pinfunction "2_2") (pintype "passive"))
      (node (ref "C30") (pin "1") (pinfunction "1_1") (pintype "passive"))
      (node (ref "C31") (pin "1") (pinfunction "1_1") (pintype "passive"))
      (node (ref "C32") (pin "1") (pinfunction "1_1") (pintype "passive"))
      (node (ref "C33") (pin "1") (pinfunction "1_1") (pintype "passive"))
      (node (ref "C34") (pin "1") (pinfunction "1_1") (pintype "passive"))
      (node (ref "C35") (pin "1") (pinfunction "1_1") (pintype "passive"))
      (node (ref "C36") (pin "1") (pinfunction "1_1") (pintype "passive"))
      (node (ref "C37") (pin "1") (pinfunction "1_1") (pintype "passive"))
      (node (ref "C38") (pin "1") (pinfunction "1_1") (pintype "passive"))
      (node (ref "C39") (pin "1") (pinfunction "1_1") (pintype "passive"))
      (node (ref "C4") (pin "2") (pinfunction "2_2") (pintype "passive"))
      (node (ref "C40") (pin "1") (pinfunction "1_1") (pintype "passive"))
      (node (ref "C41") (pin "2") (pinfunction "2_2") (pintype "passive"))
      (node (ref "C42") (pin "1") (pinfunction "1_1") (pintype "passive"))
      (node (ref "C43") (pin "2") (pinfunction "2_2") (pintype "passive"))
      (node (ref "C44") (pin "2") (pinfunction "2_2") (pintype "passive"))
      (node (ref "C45") (pin "1") (pinfunction "1_1") (pintype "passive"))
      (node (ref "C46") (pin "2") (pinfunction "2_2") (pintype "passive"))
      (node (ref "C47") (pin "1") (pinfunction "1_1") (pintype "passive"))
      (node (ref "C48") (pin "2") (pinfunction "2_2") (pintype "passive"))
      (node (ref "C5") (pin "2") (pinfunction "2_2") (pintype "passive"))
      (node (ref "C50") (pin "2") (pinfunction "2_2") (pintype "passive"))
      (node (ref "C51") (pin "1") (pinfunction "1_1") (pintype "passive"))
      (node (ref "C52") (pin "2") (pinfunction "2_2") (pintype "passive"))
      (node (ref "C53") (pin "2") (pinfunction "2_2") (pintype "passive"))
      (node (ref "C55") (pin "2") (pinfunction "2_2") (pintype "passive"))
      (node (ref "C56") (pin "2") (pinfunction "2_2") (pintype "passive"))
      (node (ref "C57") (pin "2") (pinfunction "2_2") (pintype "passive"))
      (node (ref "C58") (pin "1") (pinfunction "1_1") (pintype "passive"))
      (node (ref "C59") (pin "1") (pinfunction "1_1") (pintype "passive"))
      (node (ref "C6") (pin "2") (pinfunction "2_2") (pintype "passive"))
      (node (ref "C60") (pin "1") (pinfunction "1_1") (pintype "passive"))
      (node (ref "C7") (pin "2") (pinfunction "2_2") (pintype "passive"))
      (node (ref "C8") (pin "2") (pinfunction "2_2") (pintype "passive"))
      (node (ref "C9") (pin "2") (pinfunction "2_2") (pintype "passive"))
      (node (ref "J1") (pin "P$2") (pinfunction "2_P$2") (pintype "bidirectional"))
      (node (ref "J3") (pin "P$6") (pinfunction "VSS_P$6") (pintype "bidirectional"))
      (node (ref "J3") (pin "P$9") (pinfunction "SWITCH1_P$9") (pintype "bidirectional"))
      (node (ref "LED1") (pin "C") (pinfunction "C_C") (pintype "bidirectional"))
      (node (ref "R12") (pin "1") (pinfunction "1_1") (pintype "passive"))
      (node (ref "R13") (pin "1") (pinfunction "1_1") (pintype "passive"))
      (node (ref "R14") (pin "1") (pinfunction "1_1") (pintype "passive"))
      (node (ref "R15") (pin "1") (pinfunction "1_1") (pintype "passive"))
      (node (ref "TP13") (pin "P$1") (pinfunction "P$1_P$1") (pintype "bidirectional"))
      (node (ref "U1") (pin "P$10") (pinfunction "GND$1_P$10") (pintype "bidirectional"))
      (node (ref "U1") (pin "P$5") (pinfunction "GND$0_P$5") (pintype "bidirectional"))
      (node (ref "U10") (pin "P$12") (pinfunction "GND#0_P$12") (pintype "bidirectional"))
      (node (ref "U10") (pin "P$13") (pinfunction "GND#1_P$13") (pintype "bidirectional"))
      (node (ref "U10") (pin "P$16") (pinfunction "GND$2_P$16") (pintype "bidirectional"))
      (node (ref "U10") (pin "P$5") (pinfunction "RSVD$1_P$5") (pintype "bidirectional"))
      (node (ref "U11") (pin "P$12") (pinfunction "GND$0_P$12") (pintype "bidirectional"))
      (node (ref "U11") (pin "P$27") (pinfunction "GND$1_P$27") (pintype "bidirectional"))
      (node (ref "U11") (pin "P$3") (pinfunction "GNDA_P$3") (pintype "bidirectional"))
      (node (ref "U11") (pin "P$32") (pinfunction "~{WAKE}_P$32") (pintype "bidirectional"))
      (node (ref "U11") (pin "P$35") (pinfunction "GNDX_P$35") (pintype "bidirectional"))
      (node (ref "U11") (pin "P$39") (pinfunction "GND$2_P$39") (pintype "bidirectional"))
      (node (ref "U11") (pin "P$55") (pinfunction "GND$3_P$55") (pintype "bidirectional"))
      (node (ref "U12") (pin "2") (pinfunction "GND_2") (pintype "passive"))
      (node (ref "U12") (pin "3") (pinfunction "MODE_3") (pintype "passive"))
      (node (ref "U12") (pin "9") (pinfunction "THERMAL-PAD_9") (pintype "passive"))
      (node (ref "U13") (pin "P$4") (pinfunction "GND_P$4") (pintype "bidirectional"))
      (node (ref "U15") (pin "P$1") (pinfunction "GND_P$1") (pintype "bidirectional"))
      (node (ref "U17") (pin "P$10") (pinfunction "DEN_G_P$10") (pintype "bidirectional"))
      (node (ref "U17") (pin "P$2") (pinfunction "RES#1_P$2") (pintype "bidirectional"))
      (node (ref "U17") (pin "P$3") (pinfunction "RES#2_P$3") (pintype "bidirectional"))
      (node (ref "U17") (pin "P$4") (pinfunction "RES#3_P$4") (pintype "bidirectional"))
      (node (ref "U17") (pin "P$5") (pinfunction "GND#0_P$5") (pintype "bidirectional"))
      (node (ref "U17") (pin "P$6") (pinfunction "GND#1_P$6") (pintype "bidirectional"))
      (node (ref "U19") (pin "P$10") (pinfunction "RSVD#0_P$10") (pintype "bidirectional"))
      (node (ref "U19") (pin "P$5") (pinfunction "GND_P$5") (pintype "bidirectional"))
      (node (ref "U2") (pin "P$10") (pinfunction "RSVD#0_P$10") (pintype "bidirectional"))
      (node (ref "U2") (pin "P$12") (pinfunction "GND#1_P$12") (pintype "bidirectional"))
      (node (ref "U2") (pin "P$13") (pinfunction "GND#2_P$13") (pintype "bidirectional"))
      (node (ref "U2") (pin "P$16") (pinfunction "GND#3_P$16") (pintype "bidirectional"))
      (node (ref "U2") (pin "P$5") (pinfunction "GND#0_P$5") (pintype "bidirectional"))
      (node (ref "U21") (pin "P$8") (pinfunction "GND_P$8") (pintype "bidirectional"))
      (node (ref "U22") (pin "P$2") (pinfunction "AD0/VOUT_P$2") (pintype "bidirectional"))
      (node (ref "U22") (pin "P$3") (pinfunction "GNDD_P$3") (pintype "bidirectional"))
      (node (ref "U22") (pin "P$4") (pinfunction "GNDA_P$4") (pintype "bidirectional"))
      (node (ref "U3") (pin "P$10") (pinfunction "RSVD$1_P$10") (pintype "bidirectional"))
      (node (ref "U3") (pin "P$11") (pinfunction "RSVD$2_P$11") (pintype "bidirectional"))
      (node (ref "U3") (pin "P$12") (pinfunction "GND$0_P$12") (pintype "bidirectional"))
      (node (ref "U3") (pin "P$13") (pinfunction "GND$1_P$13") (pintype "bidirectional"))
      (node (ref "U3") (pin "P$8") (pinfunction "DEN_P$8") (pintype "bidirectional"))
      (node (ref "U3") (pin "P$9") (pinfunction "RSVD$0_P$9") (pintype "bidirectional"))
      (node (ref "U4") (pin "P$10") (pinfunction "RSVD_P$10") (pintype "bidirectional"))
      (node (ref "U4") (pin "P$11") (pinfunction "INT1_P$11") (pintype "bidirectional"))
      (node (ref "U4") (pin "P$12") (pinfunction "GND$1_P$12") (pintype "bidirectional"))
      (node (ref "U4") (pin "P$13") (pinfunction "GND$2_P$13") (pintype "bidirectional"))
      (node (ref "U4") (pin "P$16") (pinfunction "GND$3_P$16") (pintype "bidirectional"))
      (node (ref "U4") (pin "P$5") (pinfunction "GND$0_P$5") (pintype "bidirectional"))
      (node (ref "U5") (pin "P$3") (pinfunction "GND_P$3") (pintype "bidirectional"))
      (node (ref "U6") (pin "P$10") (pinfunction "RSVD_P$10") (pintype "bidirectional"))
      (node (ref "U6") (pin "P$12") (pinfunction "GND$1_P$12") (pintype "bidirectional"))
      (node (ref "U6") (pin "P$13") (pinfunction "GND$2_P$13") (pintype "bidirectional"))
      (node (ref "U6") (pin "P$16") (pinfunction "GND$3_P$16") (pintype "bidirectional"))
      (node (ref "U6") (pin "P$5") (pinfunction "GND$0_P$5") (pintype "bidirectional"))
      (node (ref "U7") (pin "2") (pinfunction "GND_2") (pintype "passive"))
      (node (ref "U7") (pin "3") (pinfunction "MODE_3") (pintype "passive"))
      (node (ref "U7") (pin "9") (pinfunction "THERMAL-PAD_9") (pintype "passive"))
      (node (ref "U8") (pin "P$1") (pinfunction "NC_P$1") (pintype "bidirectional"))
      (node (ref "U8") (pin "P$2") (pinfunction "GND$0_P$2") (pintype "bidirectional"))
      (node (ref "U8") (pin "P$5") (pinfunction "GND$1_P$5") (pintype "bidirectional"))
      (node (ref "U9") (pin "P$10") (pinfunction "RES_P$10") (pintype "bidirectional"))
      (node (ref "U9") (pin "P$12") (pinfunction "GND$1_P$12") (pintype "bidirectional"))
      (node (ref "U9") (pin "P$5") (pinfunction "GND$0_P$5") (pintype "bidirectional"))
    )
    (net (code "6") (name "IND-LED-1") (class "Default")
      (node (ref "LED2") (pin "A") (pinfunction "A_A") (pintype "bidirectional"))
      (node (ref "U11") (pin "P$45") (pinfunction "PB0_P$45") (pintype "bidirectional"))
    )
    (net (code "7") (name "IND-LED-2") (class "Default")
      (node (ref "LED3") (pin "A") (pinfunction "A_A") (pintype "bidirectional"))
      (node (ref "U11") (pin "P$46") (pinfunction "PB1_P$46") (pintype "bidirectional"))
    )
    (net (code "8") (name "IND-LED-3") (class "Default")
      (node (ref "LED4") (pin "A") (pinfunction "A_A") (pintype "bidirectional"))
      (node (ref "U11") (pin "P$47") (pinfunction "PB2_P$47") (pintype "bidirectional"))
    )
    (net (code "9") (name "IND-LED-4") (class "Default")
      (node (ref "LED5") (pin "A") (pinfunction "A_A") (pintype "bidirectional"))
      (node (ref "U11") (pin "P$48") (pinfunction "PB3_P$48") (pintype "bidirectional"))
    )
    (net (code "10") (name "INT1-MAG3110") (class "Default")
      (node (ref "U1") (pin "P$9") (pinfunction "INT1_P$9") (pintype "bidirectional"))
      (node (ref "U11") (pin "P$1") (pinfunction "PB6_P$1") (pintype "bidirectional"))
    )
    (net (code "11") (name "INT1-MPL311") (class "Default")
      (node (ref "U11") (pin "P$4") (pinfunction "PB7_P$4") (pintype "bidirectional"))
      (node (ref "U5") (pin "P$6") (pinfunction "INT1_P$6") (pintype "bidirectional"))
    )
    (net (code "12") (name "INT2-ADXL362") (class "Default")
      (node (ref "U10") (pin "P$9") (pinfunction "INT2_P$9") (pintype "bidirectional"))
      (node (ref "U11") (pin "P$5") (pinfunction "PF4_P$5") (pintype "bidirectional"))
    )
    (net (code "13") (name "INT2-H3LIS331") (class "Default")
      (node (ref "U11") (pin "P$9") (pinfunction "PE0_P$9") (pintype "bidirectional"))
      (node (ref "U2") (pin "P$9") (pinfunction "INT2_P$9") (pintype "bidirectional"))
    )
    (net (code "14") (name "INT2-L3GD") (class "Default")
      (node (ref "U11") (pin "P$15") (pinfunction "PC5_P$15") (pintype "bidirectional"))
      (node (ref "U3") (pin "P$6") (pinfunction "INT2_P$6") (pintype "bidirectional"))
    )
    (net (code "15") (name "INT2-LIS3DH") (class "Default")
      (node (ref "U11") (pin "P$14") (pinfunction "PC6_P$14") (pintype "bidirectional"))
      (node (ref "U9") (pin "P$9") (pinfunction "INT2_P$9") (pintype "bidirectional"))
    )
    (net (code "16") (name "INT2-LPS331") (class "Default")
      (node (ref "U11") (pin "P$16") (pinfunction "PC4_P$16") (pintype "bidirectional"))
      (node (ref "U4") (pin "P$9") (pinfunction "INT2_P$9") (pintype "bidirectional"))
    )
    (net (code "17") (name "INT2-LSM303") (class "Default")
      (node (ref "U11") (pin "P$10") (pinfunction "PD7_P$10") (pintype "bidirectional"))
      (node (ref "U6") (pin "P$9") (pinfunction "INT2_P$9") (pintype "bidirectional"))
    )
    (net (code "18") (name "INT2-MAX21000") (class "Default")
      (node (ref "U11") (pin "P$13") (pinfunction "PC7_P$13") (pintype "bidirectional"))
      (node (ref "U19") (pin "P$9") (pinfunction "INT2_P$9") (pintype "bidirectional"))
    )
    (net (code "19") (name "LSM9D-DRGY-G") (class "Default")
      (node (ref "U11") (pin "P$8") (pinfunction "PE1_P$8") (pintype "bidirectional"))
      (node (ref "U17") (pin "P$12") (pinfunction "DRDY_G_P$12") (pintype "bidirectional"))
    )
    (net (code "20") (name "LSM9D-INT1-XM") (class "Default")
      (node (ref "U11") (pin "P$7") (pinfunction "PE2_P$7") (pintype "bidirectional"))
      (node (ref "U17") (pin "P$13") (pinfunction "INT1_XM_P$13") (pintype "bidirectional"))
    )
    (net (code "21") (name "LSM9D-INT2-XM") (class "Default")
      (node (ref "U11") (pin "P$6") (pinfunction "PE3_P$6") (pintype "bidirectional"))
      (node (ref "U17") (pin "P$14") (pinfunction "INT2_XM_P$14") (pintype "bidirectional"))
    )
    (net (code "22") (name "MISO-A") (class "Default")
      (node (ref "U11") (pin "P$28") (pinfunction "PF0_P$28") (pintype "bidirectional"))
      (node (ref "U13") (pin "P$2") (pinfunction "3Y_P$2") (pintype "bidirectional"))
    )
    (net (code "23") (name "MISO-B") (class "Default")
      (node (ref "R6") (pin "1") (pinfunction "1_1") (pintype "passive"))
      (node (ref "U10") (pin "P$7") (pinfunction "MISO_P$7") (pintype "bidirectional"))
      (node (ref "U13") (pin "P$6") (pinfunction "3A_P$6") (pintype "bidirectional"))
      (node (ref "U15") (pin "P$6") (pinfunction "DOUT_P$6") (pintype "bidirectional"))
      (node (ref "U17") (pin "P$22") (pinfunction "SDO_G_P$22") (pintype "bidirectional"))
      (node (ref "U17") (pin "P$23") (pinfunction "SDO_XM_P$23") (pintype "bidirectional"))
      (node (ref "U19") (pin "P$7") (pinfunction "MISO_P$7") (pintype "bidirectional"))
      (node (ref "U2") (pin "P$7") (pinfunction "MISO_P$7") (pintype "bidirectional"))
      (node (ref "U3") (pin "P$4") (pinfunction "MISO_P$4") (pintype "bidirectional"))
      (node (ref "U4") (pin "P$7") (pinfunction "MISO_P$7") (pintype "bidirectional"))
      (node (ref "U6") (pin "P$7") (pinfunction "MISO_P$7") (pintype "bidirectional"))
      (node (ref "U9") (pin "P$7") (pinfunction "MISO_P$7") (pintype "bidirectional"))
    )
    (net (code "24") (name "MOSI-A") (class "Default")
      (node (ref "U11") (pin "P$29") (pinfunction "PF1_P$29") (pintype "bidirectional"))
      (node (ref "U13") (pin "P$3") (pinfunction "2A_P$3") (pintype "bidirectional"))
    )
    (net (code "25") (name "MOSI-B") (class "Default")
      (node (ref "R4") (pin "1") (pinfunction "1_1") (pintype "passive"))
      (node (ref "U10") (pin "P$6") (pinfunction "MOSI_P$6") (pintype "bidirectional"))
      (node (ref "U13") (pin "P$5") (pinfunction "2Y_P$5") (pintype "bidirectional"))
      (node (ref "U15") (pin "P$2") (pinfunction "DIN_P$2") (pintype "bidirectional"))
      (node (ref "U17") (pin "P$24") (pinfunction "SDA_P$24") (pintype "bidirectional"))
      (node (ref "U19") (pin "P$6") (pinfunction "MOSI_P$6") (pintype "bidirectional"))
      (node (ref "U2") (pin "P$6") (pinfunction "MOSI_P$6") (pintype "bidirectional"))
      (node (ref "U3") (pin "P$3") (pinfunction "MOSI_P$3") (pintype "bidirectional"))
      (node (ref "U4") (pin "P$6") (pinfunction "MOSI_P$6") (pintype "bidirectional"))
      (node (ref "U6") (pin "P$6") (pinfunction "MOSI_P$6") (pintype "bidirectional"))
      (node (ref "U9") (pin "P$6") (pinfunction "MOSI_P$6") (pintype "bidirectional"))
    )
    (net (code "26") (name "Net-(C24-Pad2)") (class "Default")
      (node (ref "C24") (pin "2") (pinfunction "2_2") (pintype "passive"))
      (node (ref "R10") (pin "1") (pinfunction "1_1") (pintype "passive"))
    )
    (net (code "27") (name "Net-(C55-Pad1)") (class "Default")
      (node (ref "C55") (pin "1") (pinfunction "1_1") (pintype "passive"))
      (node (ref "I1") (pin "1") (pinfunction "1_1") (pintype "passive"))
      (node (ref "R18") (pin "1") (pinfunction "1_1") (pintype "passive"))
      (node (ref "R9") (pin "1") (pinfunction "1_1") (pintype "passive"))
    )
    (net (code "28") (name "Net-(C56-Pad1)") (class "Default")
      (node (ref "C56") (pin "1") (pinfunction "1_1") (pintype "passive"))
      (node (ref "I2") (pin "1") (pinfunction "1_1") (pintype "passive"))
      (node (ref "R11") (pin "1") (pinfunction "1_1") (pintype "passive"))
      (node (ref "R19") (pin "1") (pinfunction "1_1") (pintype "passive"))
    )
    (net (code "29") (name "Net-(J1-1)") (class "Default")
      (node (ref "J1") (pin "P$1") (pinfunction "1_P$1") (pintype "bidirectional"))
      (node (ref "S1") (pin "2") (pinfunction "P_2") (pintype "passive"))
    )
    (net (code "30") (name "Net-(LED1-PadA)") (class "Default")
      (node (ref "LED1") (pin "A") (pinfunction "A_A") (pintype "bidirectional"))
      (node (ref "R7") (pin "1") (pinfunction "1_1") (pintype "passive"))
    )
    (net (code "31") (name "Net-(LED2-PadC)") (class "Default")
      (node (ref "LED2") (pin "C") (pinfunction "C_C") (pintype "bidirectional"))
      (node (ref "R12") (pin "2") (pinfunction "2_2") (pintype "passive"))
    )
    (net (code "32") (name "Net-(LED3-PadC)") (class "Default")
      (node (ref "LED3") (pin "C") (pinfunction "C_C") (pintype "bidirectional"))
      (node (ref "R13") (pin "2") (pinfunction "2_2") (pintype "passive"))
    )
    (net (code "33") (name "Net-(LED4-PadC)") (class "Default")
      (node (ref "LED4") (pin "C") (pinfunction "C_C") (pintype "bidirectional"))
      (node (ref "R14") (pin "2") (pinfunction "2_2") (pintype "passive"))
    )
    (net (code "34") (name "Net-(LED5-PadC)") (class "Default")
      (node (ref "LED5") (pin "C") (pinfunction "C_C") (pintype "bidirectional"))
      (node (ref "R15") (pin "2") (pinfunction "2_2") (pintype "passive"))
    )
    (net (code "35") (name "Net-(R3-Pad2)") (class "Default")
      (node (ref "R3") (pin "2") (pinfunction "2_2") (pintype "passive"))
      (node (ref "TP1") (pin "P$1") (pinfunction "P$1_P$1") (pintype "bidirectional"))
    )
    (net (code "36") (name "Net-(R4-Pad2)") (class "Default")
      (node (ref "R4") (pin "2") (pinfunction "2_2") (pintype "passive"))
      (node (ref "TP2") (pin "P$1") (pinfunction "P$1_P$1") (pintype "bidirectional"))
    )
    (net (code "37") (name "Net-(R5-Pad2)") (class "Default")
      (node (ref "R5") (pin "2") (pinfunction "2_2") (pintype "passive"))
      (node (ref "TP6") (pin "P$1") (pinfunction "P$1_P$1") (pintype "bidirectional"))
    )
    (net (code "38") (name "Net-(R6-Pad2)") (class "Default")
      (node (ref "R6") (pin "2") (pinfunction "2_2") (pintype "passive"))
      (node (ref "TP3") (pin "P$1") (pinfunction "P$1_P$1") (pintype "bidirectional"))
    )
    (net (code "39") (name "Net-(R8-Pad2)") (class "Default")
      (node (ref "R8") (pin "2") (pinfunction "2_2") (pintype "passive"))
      (node (ref "TP5") (pin "P$1") (pinfunction "P$1_P$1") (pintype "bidirectional"))
    )
    (net (code "40") (name "Net-(U1-CAP-A)") (class "Default")
      (node (ref "C1") (pin "1") (pinfunction "1_1") (pintype "passive"))
      (node (ref "U1") (pin "P$1") (pinfunction "CAP-A_P$1") (pintype "bidirectional"))
    )
    (net (code "41") (name "Net-(U1-CAP-R)") (class "Default")
      (node (ref "C4") (pin "1") (pinfunction "1_1") (pintype "passive"))
      (node (ref "U1") (pin "P$4") (pinfunction "CAP-R_P$4") (pintype "bidirectional"))
    )
    (net (code "42") (name "Net-(U3-CAP)") (class "Default")
      (node (ref "C10") (pin "1") (pinfunction "1_1") (pintype "passive"))
      (node (ref "U3") (pin "P$14") (pinfunction "CAP_P$14") (pintype "bidirectional"))
    )
    (net (code "43") (name "Net-(U5-CAP)") (class "Default")
      (node (ref "C17") (pin "1") (pinfunction "1_1") (pintype "passive"))
      (node (ref "U5") (pin "P$2") (pinfunction "CAP_P$2") (pintype "bidirectional"))
    )
    (net (code "44") (name "Net-(U6-C1)") (class "Default")
      (node (ref "C18") (pin "1") (pinfunction "1_1") (pintype "passive"))
      (node (ref "U6") (pin "P$15") (pinfunction "C1_P$15") (pintype "bidirectional"))
    )
    (net (code "45") (name "Net-(U6-SETC)") (class "Default")
      (node (ref "C21") (pin "2") (pinfunction "2_2") (pintype "passive"))
      (node (ref "U6") (pin "P$2") (pinfunction "SETC_P$2") (pintype "bidirectional"))
    )
    (net (code "46") (name "Net-(U6-SETP)") (class "Default")
      (node (ref "C21") (pin "1") (pinfunction "1_1") (pintype "passive"))
      (node (ref "U6") (pin "P$3") (pinfunction "SETP_P$3") (pintype "bidirectional"))
    )
    (net (code "47") (name "Net-(U7-PG)") (class "Default")
      (node (ref "R9") (pin "2") (pinfunction "2_2") (pintype "passive"))
      (node (ref "U7") (pin "6") (pinfunction "PG_6") (pintype "passive"))
    )
    (net (code "48") (name "Net-(U7-SW)") (class "Default")
      (node (ref "I1") (pin "2") (pinfunction "2_2") (pintype "passive"))
      (node (ref "U7") (pin "7") (pinfunction "SW_7") (pintype "passive"))
    )
    (net (code "49") (name "Net-(U11-OSC0)") (class "Default")
      (node (ref "C44") (pin "1") (pinfunction "1_1") (pintype "passive"))
      (node (ref "U11") (pin "P$40") (pinfunction "OSC0_P$40") (pintype "bidirectional"))
      (node (ref "X2") (pin "P$3") (pinfunction "B_P$3") (pintype "bidirectional"))
    )
    (net (code "50") (name "Net-(U11-OSC1)") (class "Default")
      (node (ref "R16") (pin "1") (pinfunction "1_1") (pintype "passive"))
      (node (ref "U11") (pin "P$41") (pinfunction "OSC1_P$41") (pintype "bidirectional"))
    )
    (net (code "51") (name "Net-(U11-XOSC1)") (class "Default")
      (node (ref "C42") (pin "2") (pinfunction "2_2") (pintype "passive"))
      (node (ref "U11") (pin "P$36") (pinfunction "XOSC1_P$36") (pintype "bidirectional"))
      (node (ref "X1") (pin "P$2") (pinfunction "P$2_P$2") (pintype "bidirectional"))
    )
    (net (code "52") (name "Net-(U11-XOSCO)") (class "Default")
      (node (ref "C41") (pin "1") (pinfunction "1_1") (pintype "passive"))
      (node (ref "U11") (pin "P$34") (pinfunction "XOSCO_P$34") (pintype "bidirectional"))
      (node (ref "X1") (pin "P$1") (pinfunction "P$1_P$1") (pintype "bidirectional"))
    )
    (net (code "53") (name "Net-(U11-~{RST})") (class "Default")
      (node (ref "C30") (pin "2") (pinfunction "2_2") (pintype "passive"))
      (node (ref "R17") (pin "1") (pinfunction "1_1") (pintype "passive"))
      (node (ref "U11") (pin "P$38") (pinfunction "~{RST}_P$38") (pintype "bidirectional"))
    )
    (net (code "54") (name "Net-(U12-PG)") (class "Default")
      (node (ref "R11") (pin "2") (pinfunction "2_2") (pintype "passive"))
      (node (ref "U12") (pin "6") (pinfunction "PG_6") (pintype "passive"))
    )
    (net (code "55") (name "Net-(U12-SW)") (class "Default")
      (node (ref "I2") (pin "2") (pinfunction "2_2") (pintype "passive"))
      (node (ref "U12") (pin "7") (pinfunction "SW_7") (pintype "passive"))
    )
    (net (code "56") (name "Net-(U17-C1_XM)") (class "Default")
      (node (ref "C48") (pin "1") (pinfunction "1_1") (pintype "passive"))
      (node (ref "U17") (pin "P$7") (pinfunction "C1_XM_P$7") (pintype "bidirectional"))
    )
    (net (code "57") (name "Net-(U17-SETC_XM)") (class "Default")
      (node (ref "C49") (pin "2") (pinfunction "2_2") (pintype "passive"))
      (node (ref "U17") (pin "P$8") (pinfunction "SETC_XM_P$8") (pintype "bidirectional"))
    )
    (net (code "58") (name "Net-(U17-SETP_XM)") (class "Default")
      (node (ref "C49") (pin "1") (pinfunction "1_1") (pintype "passive"))
      (node (ref "U17") (pin "P$9") (pinfunction "SETP_XM_P$9") (pintype "bidirectional"))
    )
    (net (code "59") (name "Net-(X2-A)") (class "Default")
      (node (ref "C43") (pin "1") (pinfunction "1_1") (pintype "passive"))
      (node (ref "R16") (pin "2") (pinfunction "2_2") (pintype "passive"))
      (node (ref "X2") (pin "P$1") (pinfunction "A_P$1") (pintype "bidirectional"))
    )
    (net (code "60") (name "POWER-IN") (class "Default")
      (node (ref "C50") (pin "1") (pinfunction "1_1") (pintype "passive"))
      (node (ref "C53") (pin "1") (pinfunction "1_1") (pintype "passive"))
      (node (ref "R7") (pin "2") (pinfunction "2_2") (pintype "passive"))
      (node (ref "S1") (pin "1") (pinfunction "O_1") (pintype "passive"))
      (node (ref "U12") (pin "1") (pinfunction "EN_1") (pintype "passive"))
      (node (ref "U12") (pin "8") (pinfunction "VIN_8") (pintype "passive"))
      (node (ref "U7") (pin "1") (pinfunction "EN_1") (pintype "passive"))
      (node (ref "U7") (pin "8") (pinfunction "VIN_8") (pintype "passive"))
    )
    (net (code "61") (name "SCL-0") (class "Default")
      (node (ref "R1") (pin "1") (pinfunction "1_1") (pintype "passive"))
      (node (ref "R5") (pin "1") (pinfunction "1_1") (pintype "passive"))
      (node (ref "U1") (pin "P$7") (pinfunction "SCL_P$7") (pintype "bidirectional"))
      (node (ref "U11") (pin "P$23") (pinfunction "PA6_P$23") (pintype "bidirectional"))
      (node (ref "U22") (pin "P$10") (pinfunction "SCL_P$10") (pintype "bidirectional"))
      (node (ref "U5") (pin "P$8") (pinfunction "SCL_P$8") (pintype "bidirectional"))
    )
    (net (code "62") (name "SCLK-A") (class "Default")
      (node (ref "U11") (pin "P$30") (pinfunction "PF2_P$30") (pintype "bidirectional"))
      (node (ref "U13") (pin "P$1") (pinfunction "1A_P$1") (pintype "bidirectional"))
    )
    (net (code "63") (name "SCLK-B") (class "Default")
      (node (ref "R3") (pin "1") (pinfunction "1_1") (pintype "passive"))
      (node (ref "U10") (pin "P$4") (pinfunction "SCLK_P$4") (pintype "bidirectional"))
      (node (ref "U13") (pin "P$7") (pinfunction "1Y_P$7") (pintype "bidirectional"))
      (node (ref "U15") (pin "P$4") (pinfunction "SCLK_P$4") (pintype "bidirectional"))
      (node (ref "U17") (pin "P$21") (pinfunction "SCL_P$21") (pintype "bidirectional"))
      (node (ref "U19") (pin "P$4") (pinfunction "SCLK_P$4") (pintype "bidirectional"))
      (node (ref "U2") (pin "P$4") (pinfunction "SCLK_P$4") (pintype "bidirectional"))
      (node (ref "U3") (pin "P$2") (pinfunction "SCL_P$2") (pintype "bidirectional"))
      (node (ref "U4") (pin "P$4") (pinfunction "SCL_P$4") (pintype "bidirectional"))
      (node (ref "U6") (pin "P$4") (pinfunction "SCL_P$4") (pintype "bidirectional"))
      (node (ref "U9") (pin "P$4") (pinfunction "SCL_P$4") (pintype "bidirectional"))
    )
    (net (code "64") (name "SD-CARD-INSERT") (class "Default")
      (node (ref "J3") (pin "P$8") (pinfunction "SWITCH2_P$8") (pintype "bidirectional"))
      (node (ref "U11") (pin "P$60") (pinfunction "PE5_P$60") (pintype "bidirectional"))
    )
    (net (code "65") (name "SD-CS") (class "Default")
      (node (ref "J3") (pin "P$2") (pinfunction "~{CS}_P$2") (pintype "bidirectional"))
      (node (ref "U11") (pin "P$62") (pinfunction "PD1_P$62") (pintype "bidirectional"))
    )
    (net (code "66") (name "SD-MISO") (class "Default")
      (node (ref "J3") (pin "P$7") (pinfunction "D0_P$7") (pintype "bidirectional"))
      (node (ref "U11") (pin "P$63") (pinfunction "PD2_P$63") (pintype "bidirectional"))
    )
    (net (code "67") (name "SD-MOSI") (class "Default")
      (node (ref "J3") (pin "P$3") (pinfunction "DI_P$3") (pintype "bidirectional"))
      (node (ref "U11") (pin "P$64") (pinfunction "PD3_P$64") (pintype "bidirectional"))
    )
    (net (code "68") (name "SD-SCLK") (class "Default")
      (node (ref "J3") (pin "P$5") (pinfunction "SCLK_P$5") (pintype "bidirectional"))
      (node (ref "U11") (pin "P$61") (pinfunction "PD0_P$61") (pintype "bidirectional"))
    )
    (net (code "69") (name "SDA-0") (class "Default")
      (node (ref "R2") (pin "1") (pinfunction "1_1") (pintype "passive"))
      (node (ref "R8") (pin "1") (pinfunction "1_1") (pintype "passive"))
      (node (ref "U1") (pin "P$6") (pinfunction "SDA_P$6") (pintype "bidirectional"))
      (node (ref "U11") (pin "P$24") (pinfunction "PA7_P$24") (pintype "bidirectional"))
      (node (ref "U22") (pin "P$1") (pinfunction "SDA_P$1") (pintype "bidirectional"))
      (node (ref "U5") (pin "P$7") (pinfunction "SDA_P$7") (pintype "bidirectional"))
    )
    (net (code "70") (name "SPI-ADDR0") (class "Default")
      (node (ref "U11") (pin "P$17") (pinfunction "PA0_P$17") (pintype "bidirectional"))
      (node (ref "U21") (pin "P$15") (pinfunction "A_P$15") (pintype "bidirectional"))
    )
    (net (code "71") (name "SPI-ADDR1") (class "Default")
      (node (ref "U11") (pin "P$18") (pinfunction "PA1_P$18") (pintype "bidirectional"))
      (node (ref "U21") (pin "P$14") (pinfunction "B_P$14") (pintype "bidirectional"))
    )
    (net (code "72") (name "SPI-ADDR2") (class "Default")
      (node (ref "U11") (pin "P$19") (pinfunction "PA2_P$19") (pintype "bidirectional"))
      (node (ref "U21") (pin "P$13") (pinfunction "C_P$13") (pintype "bidirectional"))
    )
    (net (code "73") (name "SPI-ADDR3") (class "Default")
      (node (ref "U11") (pin "P$20") (pinfunction "PA3_P$20") (pintype "bidirectional"))
      (node (ref "U21") (pin "P$12") (pinfunction "D_P$12") (pintype "bidirectional"))
    )
    (net (code "74") (name "SPI-ENABLE") (class "Default")
      (node (ref "U11") (pin "P$31") (pinfunction "PF3_P$31") (pintype "bidirectional"))
    )
    (net (code "75") (name "SWCLK") (class "Default")
      (node (ref "J4") (pin "P$1") (pinfunction "1_P$1") (pintype "bidirectional"))
      (node (ref "U11") (pin "P$52") (pinfunction "PC0_P$52") (pintype "bidirectional"))
    )
    (net (code "76") (name "SWDIO") (class "Default")
      (node (ref "J4") (pin "P$2") (pinfunction "2_P$2") (pintype "bidirectional"))
      (node (ref "U11") (pin "P$51") (pinfunction "PC1_P$51") (pintype "bidirectional"))
    )
    (net (code "77") (name "SWO") (class "Default")
      (node (ref "J4") (pin "P$4") (pinfunction "4_P$4") (pintype "bidirectional"))
      (node (ref "U11") (pin "P$49") (pinfunction "PC3_P$49") (pintype "bidirectional"))
    )
    (net (code "78") (name "TDI") (class "Default")
      (node (ref "J4") (pin "P$3") (pinfunction "3_P$3") (pintype "bidirectional"))
      (node (ref "U11") (pin "P$50") (pinfunction "PC2_P$50") (pintype "bidirectional"))
    )
    (net (code "79") (name "U6RX") (class "Default")
      (node (ref "J2") (pin "P$1") (pinfunction "1_P$1") (pintype "bidirectional"))
      (node (ref "TP8") (pin "P$1") (pinfunction "P$1_P$1") (pintype "bidirectional"))
      (node (ref "U11") (pin "P$43") (pinfunction "PD4_P$43") (pintype "bidirectional"))
    )
    (net (code "80") (name "U6TX") (class "Default")
      (node (ref "J2") (pin "P$2") (pinfunction "2_P$2") (pintype "bidirectional"))
      (node (ref "TP7") (pin "P$1") (pinfunction "P$1_P$1") (pintype "bidirectional"))
      (node (ref "U11") (pin "P$44") (pinfunction "PD5_P$44") (pintype "bidirectional"))
    )
    (net (code "81") (name "unconnected-(J3-GND#1-PadP$10)") (class "Default")
      (node (ref "J3") (pin "P$10") (pinfunction "GND#1_P$10") (pintype "bidirectional"))
    )
    (net (code "82") (name "unconnected-(J3-GND#2-PadP$11)") (class "Default")
      (node (ref "J3") (pin "P$11") (pinfunction "GND#2_P$11") (pintype "bidirectional"))
    )
    (net (code "83") (name "unconnected-(J3-GND#3-PadP$12)") (class "Default")
      (node (ref "J3") (pin "P$12") (pinfunction "GND#3_P$12") (pintype "bidirectional"))
    )
    (net (code "84") (name "unconnected-(J3-GND#4-PadP$13)") (class "Default")
      (node (ref "J3") (pin "P$13") (pinfunction "GND#4_P$13") (pintype "bidirectional"))
    )
    (net (code "85") (name "unconnected-(J3-RSV-PadP$1)") (class "Default")
      (node (ref "J3") (pin "P$1") (pinfunction "RSV_P$1") (pintype "bidirectional"))
    )
    (net (code "86") (name "unconnected-(S1-S-Pad3)") (class "Default")
      (node (ref "S1") (pin "3") (pinfunction "S_3") (pintype "passive"))
    )
    (net (code "87") (name "unconnected-(U1-NC-PadP$3)") (class "Default")
      (node (ref "U1") (pin "P$3") (pinfunction "NC_P$3") (pintype "bidirectional"))
    )
    (net (code "88") (name "unconnected-(U2-INT1-PadP$11)") (class "Default")
      (node (ref "U2") (pin "P$11") (pinfunction "INT1_P$11") (pintype "bidirectional"))
    )
    (net (code "89") (name "unconnected-(U2-NC#0-PadP$2)") (class "Default")
      (node (ref "U2") (pin "P$2") (pinfunction "NC#0_P$2") (pintype "bidirectional"))
    )
    (net (code "90") (name "unconnected-(U2-NC#1-PadP$3)") (class "Default")
      (node (ref "U2") (pin "P$3") (pinfunction "NC#1_P$3") (pintype "bidirectional"))
    )
    (net (code "91") (name "unconnected-(U3-INT1-PadP$7)") (class "Default")
      (node (ref "U3") (pin "P$7") (pinfunction "INT1_P$7") (pintype "bidirectional"))
    )
    (net (code "92") (name "unconnected-(U4-NC$0-PadP$2)") (class "Default")
      (node (ref "U4") (pin "P$2") (pinfunction "NC$0_P$2") (pintype "bidirectional"))
    )
    (net (code "93") (name "unconnected-(U4-NC$1-PadP$3)") (class "Default")
      (node (ref "U4") (pin "P$3") (pinfunction "NC$1_P$3") (pintype "bidirectional"))
    )
    (net (code "94") (name "unconnected-(U5-INT2-PadP$5)") (class "Default")
      (node (ref "U5") (pin "P$5") (pinfunction "INT2_P$5") (pintype "bidirectional"))
    )
    (net (code "95") (name "unconnected-(U6-INT1-PadP$11)") (class "Default")
      (node (ref "U6") (pin "P$11") (pinfunction "INT1_P$11") (pintype "bidirectional"))
    )
    (net (code "96") (name "unconnected-(U7-FB-Pad4)") (class "Default")
      (node (ref "U7") (pin "4") (pinfunction "FB_4") (pintype "passive"))
    )
    (net (code "97") (name "unconnected-(U7-VOS-Pad5)") (class "Default")
      (node (ref "U7") (pin "5") (pinfunction "VOS_5") (pintype "passive"))
    )
    (net (code "98") (name "unconnected-(U9-ADC1-PadP$16)") (class "Default")
      (node (ref "U9") (pin "P$16") (pinfunction "ADC1_P$16") (pintype "bidirectional"))
    )
    (net (code "99") (name "unconnected-(U9-ADC2-PadP$15)") (class "Default")
      (node (ref "U9") (pin "P$15") (pinfunction "ADC2_P$15") (pintype "bidirectional"))
    )
    (net (code "100") (name "unconnected-(U9-ADC3-PadP$13)") (class "Default")
      (node (ref "U9") (pin "P$13") (pinfunction "ADC3_P$13") (pintype "bidirectional"))
    )
    (net (code "101") (name "unconnected-(U9-INT1-PadP$11)") (class "Default")
      (node (ref "U9") (pin "P$11") (pinfunction "INT1_P$11") (pintype "bidirectional"))
    )
    (net (code "102") (name "unconnected-(U9-NC$0-PadP$2)") (class "Default")
      (node (ref "U9") (pin "P$2") (pinfunction "NC$0_P$2") (pintype "bidirectional"))
    )
    (net (code "103") (name "unconnected-(U9-NC$1-PadP$3)") (class "Default")
      (node (ref "U9") (pin "P$3") (pinfunction "NC$1_P$3") (pintype "bidirectional"))
    )
    (net (code "104") (name "unconnected-(U10-INT1-PadP$11)") (class "Default")
      (node (ref "U10") (pin "P$11") (pinfunction "INT1_P$11") (pintype "bidirectional"))
    )
    (net (code "105") (name "unconnected-(U10-NC$0-PadP$2)") (class "Default")
      (node (ref "U10") (pin "P$2") (pinfunction "NC$0_P$2") (pintype "bidirectional"))
    )
    (net (code "106") (name "unconnected-(U10-NC$1-PadP$15)") (class "Default")
      (node (ref "U10") (pin "P$15") (pinfunction "NC$1_P$15") (pintype "bidirectional"))
    )
    (net (code "107") (name "unconnected-(U10-RSVD$0-PadP$3)") (class "Default")
      (node (ref "U10") (pin "P$3") (pinfunction "RSVD$0_P$3") (pintype "bidirectional"))
    )
    (net (code "108") (name "unconnected-(U10-RSVD$2-PadP$10)") (class "Default")
      (node (ref "U10") (pin "P$10") (pinfunction "RSVD$2_P$10") (pintype "bidirectional"))
    )
    (net (code "109") (name "unconnected-(U11-PA4-PadP$21)") (class "Default")
      (node (ref "U11") (pin "P$21") (pinfunction "PA4_P$21") (pintype "bidirectional"))
    )
    (net (code "110") (name "unconnected-(U11-PA5-PadP$22)") (class "Default")
      (node (ref "U11") (pin "P$22") (pinfunction "PA5_P$22") (pintype "bidirectional"))
    )
    (net (code "111") (name "unconnected-(U11-PB5-PadP$57)") (class "Default")
      (node (ref "U11") (pin "P$57") (pinfunction "PB5_P$57") (pintype "bidirectional"))
    )
    (net (code "112") (name "unconnected-(U11-PD6-PadP$53)") (class "Default")
      (node (ref "U11") (pin "P$53") (pinfunction "PD6_P$53") (pintype "bidirectional"))
    )
    (net (code "113") (name "unconnected-(U11-PE4-PadP$59)") (class "Default")
      (node (ref "U11") (pin "P$59") (pinfunction "PE4_P$59") (pintype "bidirectional"))
    )
    (net (code "114") (name "unconnected-(U11-~{HIB}-PadP$33)") (class "Default")
      (node (ref "U11") (pin "P$33") (pinfunction "~{HIB}_P$33") (pintype "bidirectional"))
    )
    (net (code "115") (name "unconnected-(U12-FB-Pad4)") (class "Default")
      (node (ref "U12") (pin "4") (pinfunction "FB_4") (pintype "passive"))
    )
    (net (code "116") (name "unconnected-(U12-VOS-Pad5)") (class "Default")
      (node (ref "U12") (pin "5") (pinfunction "VOS_5") (pintype "passive"))
    )
    (net (code "117") (name "unconnected-(U17-INT_G-PadP$11)") (class "Default")
      (node (ref "U17") (pin "P$11") (pinfunction "INT_G_P$11") (pintype "bidirectional"))
    )
    (net (code "118") (name "unconnected-(U17-RES#0-PadP$1)") (class "Default")
      (node (ref "U17") (pin "P$1") (pinfunction "RES#0_P$1") (pintype "bidirectional"))
    )
    (net (code "119") (name "unconnected-(U19-DSYNC-PadP$12)") (class "Default")
      (node (ref "U19") (pin "P$12") (pinfunction "DSYNC_P$12") (pintype "bidirectional"))
    )
    (net (code "120") (name "unconnected-(U19-INT1-PadP$11)") (class "Default")
      (node (ref "U19") (pin "P$11") (pinfunction "INT1_P$11") (pintype "bidirectional"))
    )
    (net (code "121") (name "unconnected-(U19-NC#0-PadP$2)") (class "Default")
      (node (ref "U19") (pin "P$2") (pinfunction "NC#0_P$2") (pintype "bidirectional"))
    )
    (net (code "122") (name "unconnected-(U19-NC#1-PadP$3)") (class "Default")
      (node (ref "U19") (pin "P$3") (pinfunction "NC#1_P$3") (pintype "bidirectional"))
    )
    (net (code "123") (name "unconnected-(U19-NC#2-PadP$16)") (class "Default")
      (node (ref "U19") (pin "P$16") (pinfunction "NC#2_P$16") (pintype "bidirectional"))
    )
    (net (code "124") (name "unconnected-(U19-RSVD#1-PadP$13)") (class "Default")
      (node (ref "U19") (pin "P$13") (pinfunction "RSVD#1_P$13") (pintype "bidirectional"))
    )
    (net (code "125") (name "unconnected-(U22-FLOAT-PadP$11)") (class "Default")
      (node (ref "U22") (pin "P$11") (pinfunction "FLOAT_P$11") (pintype "bidirectional"))
    )
    (net (code "126") (name "unconnected-(U22-VINN-PadP$7)") (class "Default")
      (node (ref "U22") (pin "P$7") (pinfunction "VINN_P$7") (pintype "bidirectional"))
    )
    (net (code "127") (name "unconnected-(U22-VINP-PadP$6)") (class "Default")
      (node (ref "U22") (pin "P$6") (pinfunction "VINP_P$6") (pintype "bidirectional"))
    )
    (net (code "128") (name "~{CS-ADT7301}") (class "Default")
      (node (ref "U15") (pin "P$5") (pinfunction "~{CS}_P$5") (pintype "bidirectional"))
      (node (ref "U21") (pin "P$11") (pinfunction "9_P$11") (pintype "bidirectional"))
    )
    (net (code "129") (name "~{CS-ADXL362}") (class "Default")
      (node (ref "U10") (pin "P$8") (pinfunction "~{CS}_P$8") (pintype "bidirectional"))
      (node (ref "U21") (pin "P$1") (pinfunction "0_P$1") (pintype "bidirectional"))
    )
    (net (code "130") (name "~{CS-H3LIS331DLTR}") (class "Default")
      (node (ref "U2") (pin "P$8") (pinfunction "~{CS}_P$8") (pintype "bidirectional"))
      (node (ref "U21") (pin "P$2") (pinfunction "1_P$2") (pintype "bidirectional"))
    )
    (net (code "131") (name "~{CS-LIS3DH}") (class "Default")
      (node (ref "U21") (pin "P$7") (pinfunction "6_P$7") (pintype "bidirectional"))
      (node (ref "U9") (pin "P$8") (pinfunction "~{CS}_P$8") (pintype "bidirectional"))
    )
    (net (code "132") (name "~{CS-LPS331}") (class "Default")
      (node (ref "U21") (pin "P$10") (pinfunction "8_P$10") (pintype "bidirectional"))
      (node (ref "U4") (pin "P$8") (pinfunction "~{CS}_P$8") (pintype "bidirectional"))
    )
    (net (code "133") (name "~{CS-LS3GD20}") (class "Default")
      (node (ref "U21") (pin "P$9") (pinfunction "7_P$9") (pintype "bidirectional"))
      (node (ref "U3") (pin "P$5") (pinfunction "~{CS}_P$5") (pintype "bidirectional"))
    )
    (net (code "134") (name "~{CS-LSM9D30-G}") (class "Default")
      (node (ref "U17") (pin "P$19") (pinfunction "~{CS_G}_P$19") (pintype "bidirectional"))
      (node (ref "U21") (pin "P$3") (pinfunction "2_P$3") (pintype "bidirectional"))
    )
    (net (code "135") (name "~{CS-LSM9DS0-XM}") (class "Default")
      (node (ref "U17") (pin "P$20") (pinfunction "~{CS_XM}_P$20") (pintype "bidirectional"))
      (node (ref "U21") (pin "P$4") (pinfunction "3_P$4") (pintype "bidirectional"))
    )
    (net (code "136") (name "~{CS-LSM303}") (class "Default")
      (node (ref "U21") (pin "P$6") (pinfunction "5_P$6") (pintype "bidirectional"))
      (node (ref "U6") (pin "P$8") (pinfunction "~{CS}_P$8") (pintype "bidirectional"))
    )
    (net (code "137") (name "~{CS-MAX21000}") (class "Default")
      (node (ref "U19") (pin "P$8") (pinfunction "~{CS}_P$8") (pintype "bidirectional"))
      (node (ref "U21") (pin "P$5") (pinfunction "4_P$5") (pintype "bidirectional"))
    )
  )
)
